# schody_v2.net
KiCad netlist of a schematic drawn in EAGLE
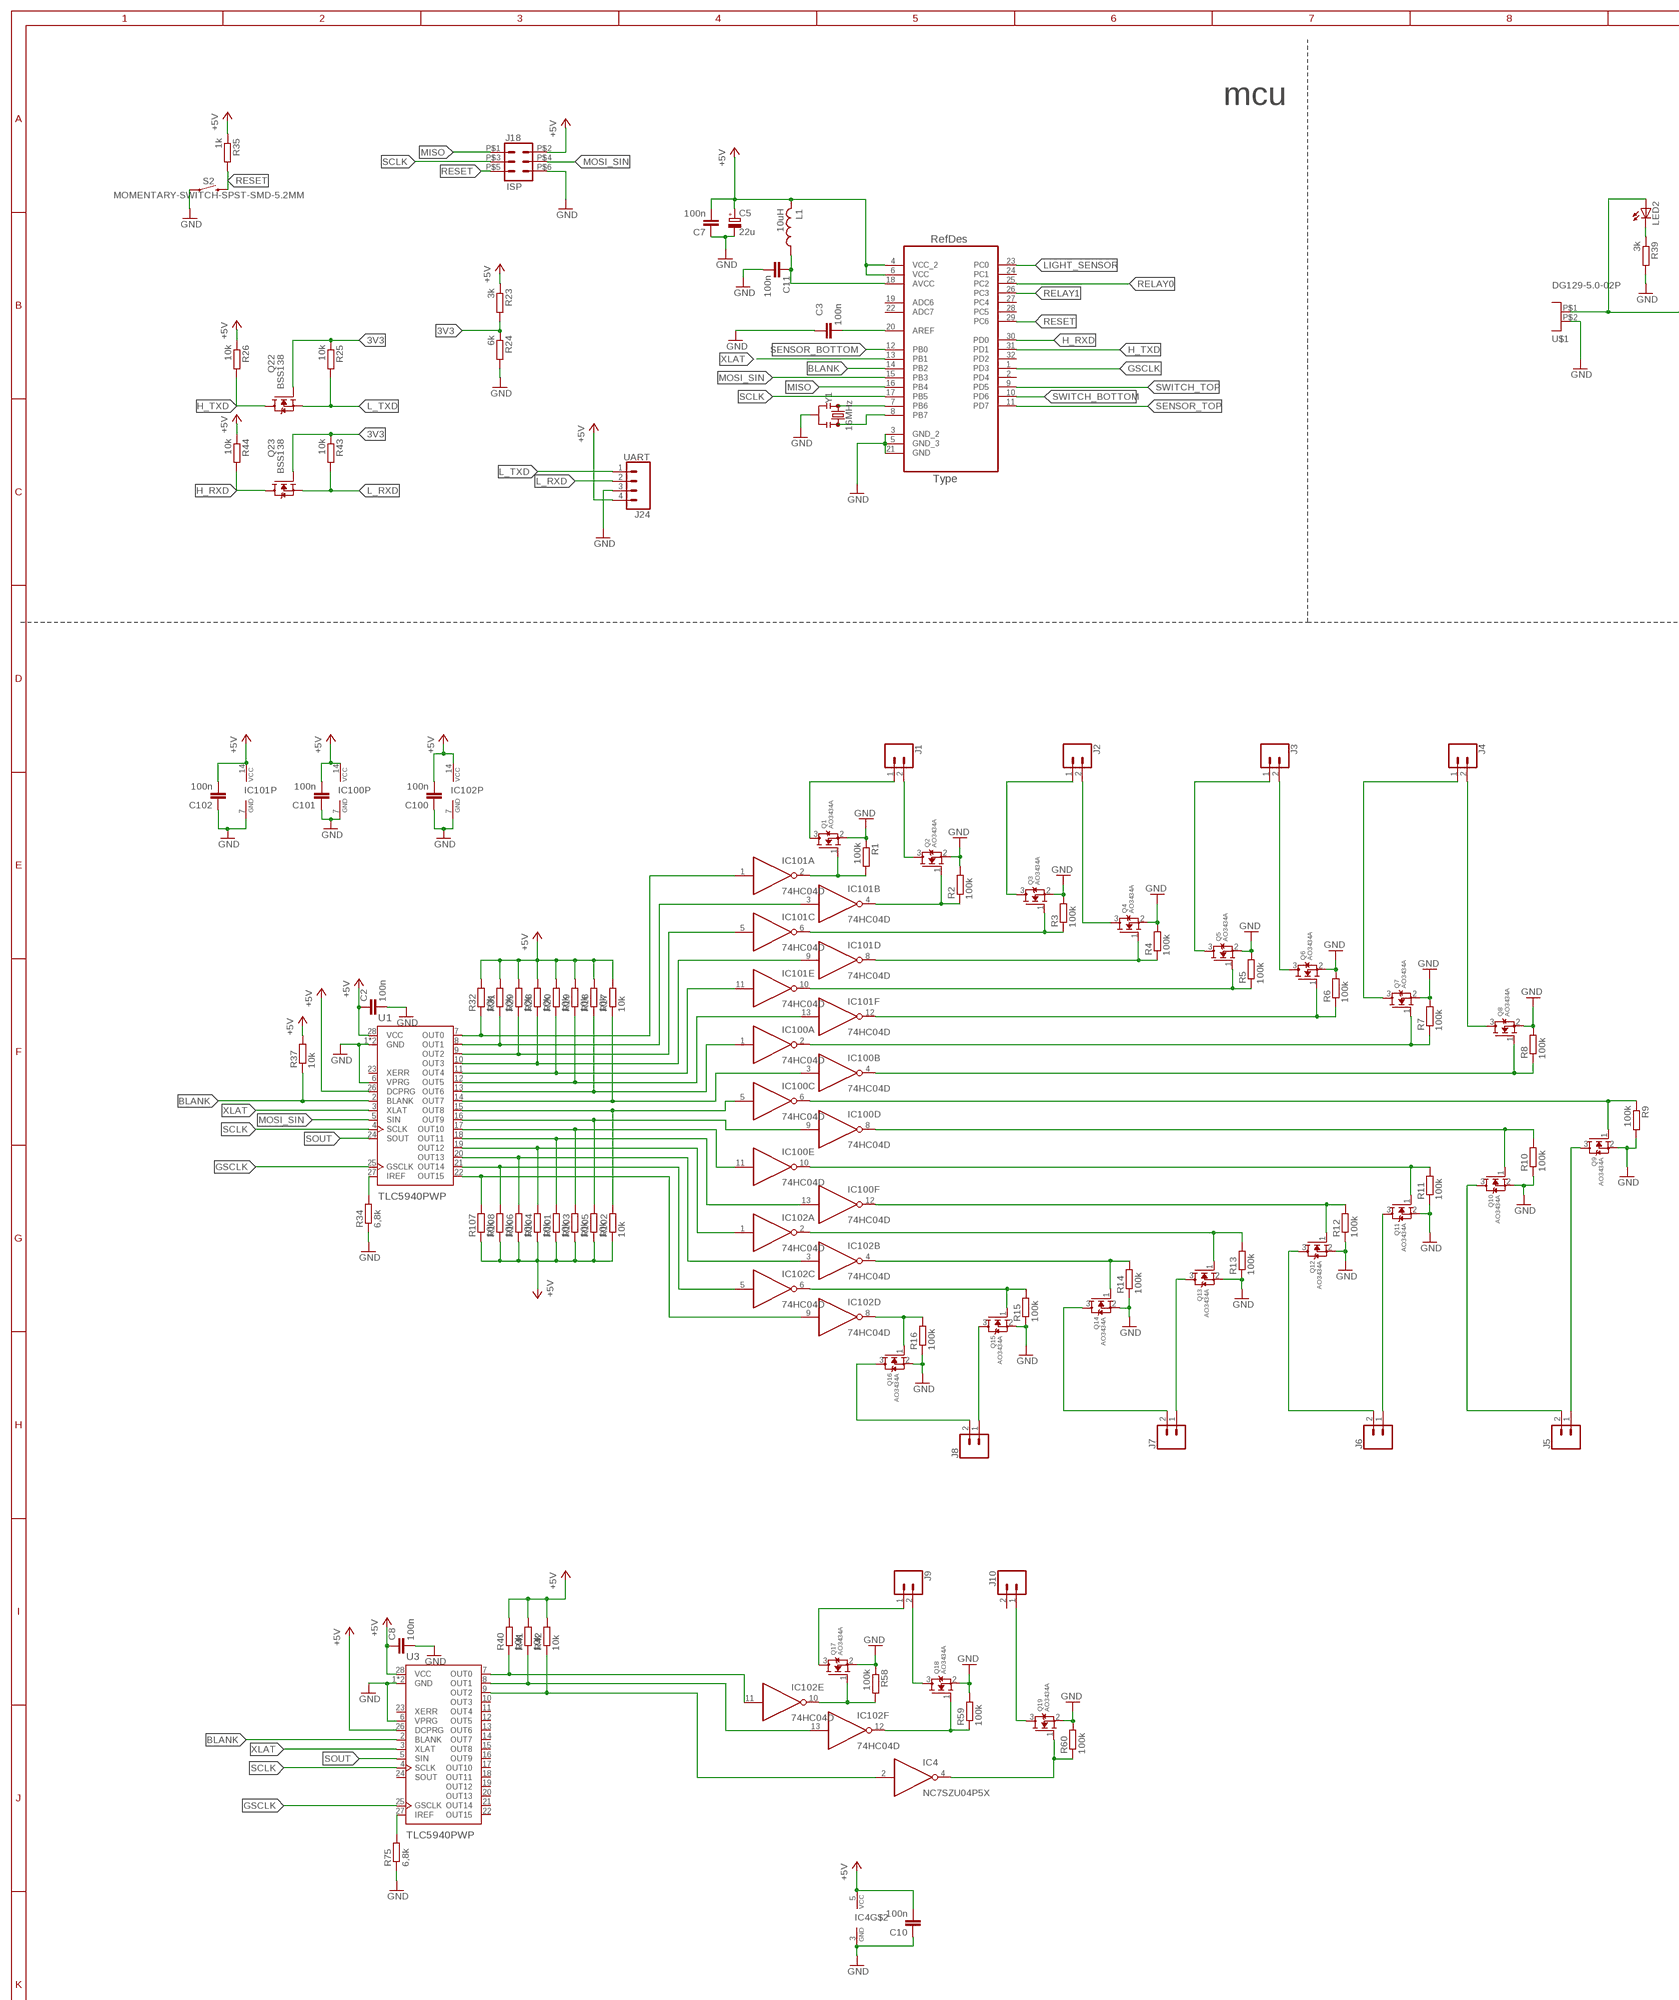
[diagram p0: schematic, sheet 1, part 1 of 3]
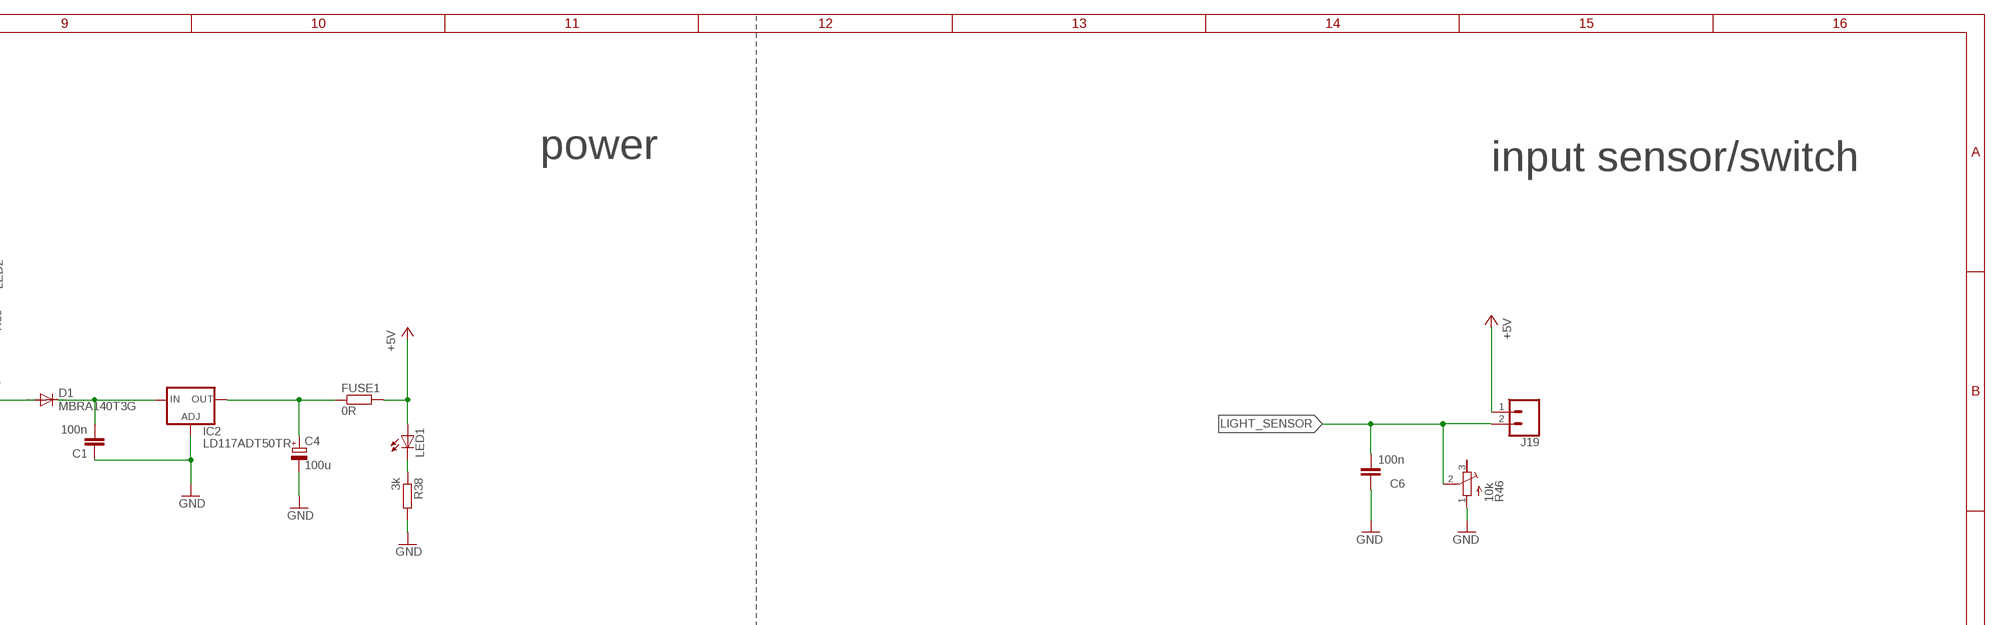
[diagram p1: schematic, sheet 1, part 2 of 3]
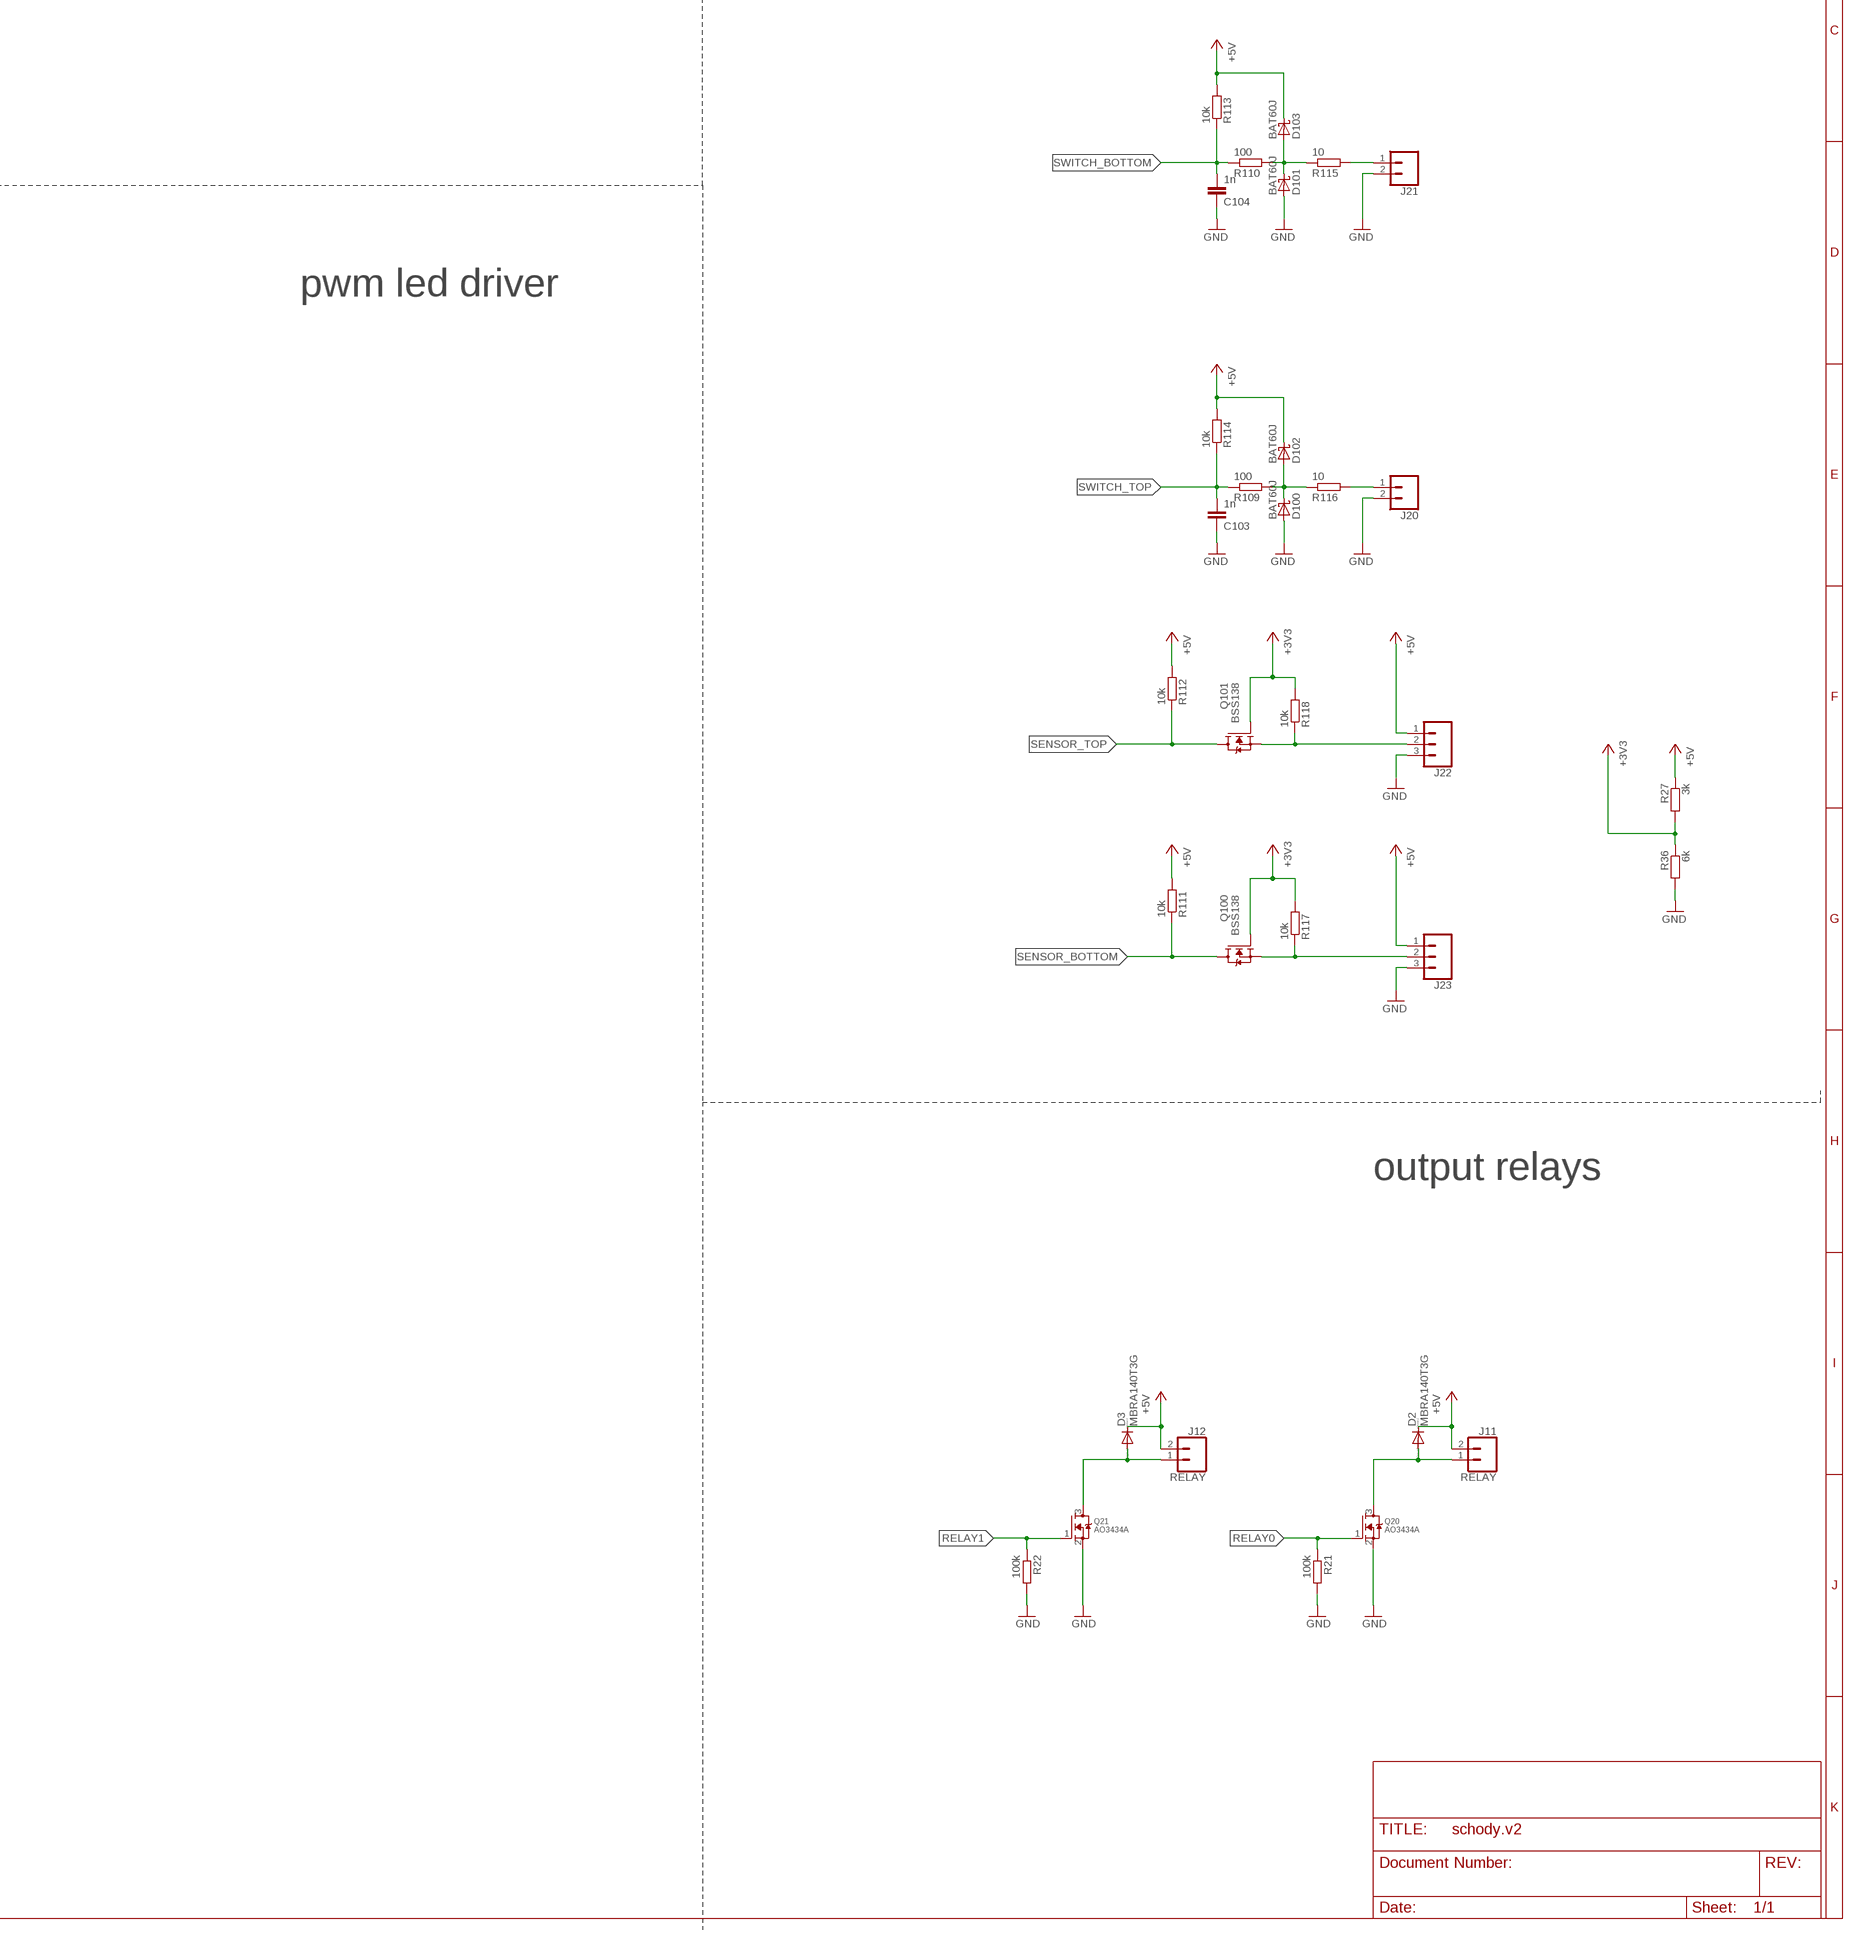
[diagram p2: schematic, sheet 1, part 3 of 3]

(export (version "E")
  (design (tool "Eeschema 10.0.6"))
  (components
    (comp (ref "C1")
      (value "100n")
      (footprint "eagle-import:C0805K")
      (libsource (lib "eagle-import") (part "C-EUC0805K"))
    )
    (comp (ref "C2")
      (value "100n")
      (footprint "eagle-import:C0805K")
      (libsource (lib "eagle-import") (part "C-EUC0805K"))
    )
    (comp (ref "C3")
      (value "100n")
      (footprint "eagle-import:C0805")
      (libsource (lib "eagle-import") (part "C-EUC0805"))
    )
    (comp (ref "C4")
      (value "100u")
      (footprint "eagle-import:SMC_D")
      (libsource (lib "eagle-import") (part "CPOL-EUSMCD"))
    )
    (comp (ref "C5")
      (value "22u")
      (footprint "eagle-import:SMC_E")
      (libsource (lib "eagle-import") (part "CPOL-EUSMCE"))
    )
    (comp (ref "C6")
      (value "100n")
      (footprint "eagle-import:C0805")
      (libsource (lib "eagle-import") (part "C-EUC0805"))
    )
    (comp (ref "C7")
      (value "100n")
      (footprint "eagle-import:C0805")
      (libsource (lib "eagle-import") (part "C-EUC0805"))
    )
    (comp (ref "C8")
      (value "100n")
      (footprint "eagle-import:C0805K")
      (libsource (lib "eagle-import") (part "C-EUC0805K"))
    )
    (comp (ref "C10")
      (value "100n")
      (footprint "eagle-import:C0805K")
      (libsource (lib "eagle-import") (part "C-EUC0805K"))
    )
    (comp (ref "C11")
      (value "100n")
      (footprint "eagle-import:C0805")
      (libsource (lib "eagle-import") (part "C-EUC0805"))
    )
    (comp (ref "C100")
      (value "100n")
      (footprint "eagle-import:C0805K")
      (libsource (lib "eagle-import") (part "C-EUC0805K"))
    )
    (comp (ref "C101")
      (value "100n")
      (footprint "eagle-import:C0805K")
      (libsource (lib "eagle-import") (part "C-EUC0805K"))
    )
    (comp (ref "C102")
      (value "100n")
      (footprint "eagle-import:C0805K")
      (libsource (lib "eagle-import") (part "C-EUC0805K"))
    )
    (comp (ref "C103")
      (value "1n")
      (footprint "eagle-import:C0805K")
      (libsource (lib "eagle-import") (part "C-EUC0805K"))
    )
    (comp (ref "C104")
      (value "1n")
      (footprint "eagle-import:C0805K")
      (libsource (lib "eagle-import") (part "C-EUC0805K"))
    )
    (comp (ref "D1")
      (value "MBRA140T3G")
      (footprint "eagle-import:DO214BA")
      (libsource (lib "eagle-import") (part "DIODE-DO214BA"))
    )
    (comp (ref "D2")
      (value "MBRA140T3G")
      (footprint "eagle-import:DO214BA")
      (libsource (lib "eagle-import") (part "DIODE-DO214BA"))
    )
    (comp (ref "D3")
      (value "MBRA140T3G")
      (footprint "eagle-import:DO214BA")
      (libsource (lib "eagle-import") (part "DIODE-DO214BA"))
    )
    (comp (ref "D100")
      (value "BAT60J")
      (footprint "eagle-import:SOD323_ST")
      (fields (field (name "SPICEPREFIX") "D"))
      (libsource (lib "eagle-import") (part "BAT60J"))
    )
    (comp (ref "D101")
      (value "BAT60J")
      (footprint "eagle-import:SOD323_ST")
      (libsource (lib "eagle-import") (part "BAT60J"))
    )
    (comp (ref "D102")
      (value "BAT60J")
      (footprint "eagle-import:SOD323_ST")
      (fields (field (name "SPICEPREFIX") "D"))
      (libsource (lib "eagle-import") (part "BAT60J"))
    )
    (comp (ref "D103")
      (value "BAT60J")
      (footprint "eagle-import:SOD323_ST")
      (libsource (lib "eagle-import") (part "BAT60J"))
    )
    (comp (ref "FUSE1")
      (value "0R")
      (footprint "eagle-import:M1206")
      (libsource (lib "eagle-import") (part "R-EU_M1206"))
    )
    (comp (ref "IC2")
      (value "LD117ADT50TR")
      (footprint "eagle-import:DPACK")
      (libsource (lib "eagle-import") (part "LD117A?DT50TR"))
    )
    (comp (ref "IC4")
      (value "NC7SZU04P5X")
      (footprint "eagle-import:SC70-5")
      (libsource (lib "eagle-import") (part "741GU04DCKAHC"))
    )
    (comp (ref "IC100")
      (value "74HC04D")
      (footprint "eagle-import:SO14")
      (libsource (lib "eagle-import") (part "7404DHC"))
    )
    (comp (ref "IC101")
      (value "74HC04D")
      (footprint "eagle-import:SO14")
      (libsource (lib "eagle-import") (part "7404DHC"))
    )
    (comp (ref "IC102")
      (value "74HC04D")
      (footprint "eagle-import:SO14")
      (libsource (lib "eagle-import") (part "7404DHC"))
    )
    (comp (ref "J1")
      (value "CONN_023.5MM")
      (footprint "eagle-import:SCREWTERMINAL-3.5MM-2")
      (libsource (lib "eagle-import") (part "CONN_023.5MM"))
    )
    (comp (ref "J2")
      (value "CONN_023.5MM")
      (footprint "eagle-import:SCREWTERMINAL-3.5MM-2")
      (libsource (lib "eagle-import") (part "CONN_023.5MM"))
    )
    (comp (ref "J3")
      (value "CONN_023.5MM")
      (footprint "eagle-import:SCREWTERMINAL-3.5MM-2")
      (libsource (lib "eagle-import") (part "CONN_023.5MM"))
    )
    (comp (ref "J4")
      (value "CONN_023.5MM")
      (footprint "eagle-import:SCREWTERMINAL-3.5MM-2")
      (libsource (lib "eagle-import") (part "CONN_023.5MM"))
    )
    (comp (ref "J5")
      (value "CONN_023.5MM")
      (footprint "eagle-import:SCREWTERMINAL-3.5MM-2")
      (libsource (lib "eagle-import") (part "CONN_023.5MM"))
    )
    (comp (ref "J6")
      (value "CONN_023.5MM")
      (footprint "eagle-import:SCREWTERMINAL-3.5MM-2")
      (libsource (lib "eagle-import") (part "CONN_023.5MM"))
    )
    (comp (ref "J7")
      (value "CONN_023.5MM")
      (footprint "eagle-import:SCREWTERMINAL-3.5MM-2")
      (libsource (lib "eagle-import") (part "CONN_023.5MM"))
    )
    (comp (ref "J8")
      (value "CONN_023.5MM")
      (footprint "eagle-import:SCREWTERMINAL-3.5MM-2")
      (libsource (lib "eagle-import") (part "CONN_023.5MM"))
    )
    (comp (ref "J9")
      (value "CONN_023.5MM")
      (footprint "eagle-import:SCREWTERMINAL-3.5MM-2")
      (libsource (lib "eagle-import") (part "CONN_023.5MM"))
    )
    (comp (ref "J10")
      (value "CONN_023.5MM")
      (footprint "eagle-import:SCREWTERMINAL-3.5MM-2")
      (libsource (lib "eagle-import") (part "CONN_023.5MM"))
    )
    (comp (ref "J11")
      (value "RELAY")
      (footprint "eagle-import:SCREWTERMINAL-3.5MM-2")
      (libsource (lib "eagle-import") (part "CONN_023.5MM"))
    )
    (comp (ref "J12")
      (value "RELAY")
      (footprint "eagle-import:SCREWTERMINAL-3.5MM-2")
      (libsource (lib "eagle-import") (part "CONN_023.5MM"))
    )
    (comp (ref "J18")
      (value "ISP")
      (footprint "eagle-import:2X3_POGO")
      (libsource (lib "eagle-import") (part "CONN_03X2POGO_PINS"))
    )
    (comp (ref "J19")
      (value "CONN_023.5MM")
      (footprint "eagle-import:SCREWTERMINAL-3.5MM-2")
      (libsource (lib "eagle-import") (part "CONN_023.5MM"))
    )
    (comp (ref "J20")
      (value "CONN_023.5MM")
      (footprint "eagle-import:SCREWTERMINAL-3.5MM-2")
      (libsource (lib "eagle-import") (part "CONN_023.5MM"))
    )
    (comp (ref "J21")
      (value "CONN_023.5MM")
      (footprint "eagle-import:SCREWTERMINAL-3.5MM-2")
      (libsource (lib "eagle-import") (part "CONN_023.5MM"))
    )
    (comp (ref "J22")
      (value "CONN_03SCREW")
      (footprint "eagle-import:SCREWTERMINAL-3.5MM-3")
      (libsource (lib "eagle-import") (part "CONN_03SCREW"))
    )
    (comp (ref "J23")
      (value "CONN_03SCREW")
      (footprint "eagle-import:SCREWTERMINAL-3.5MM-3")
      (libsource (lib "eagle-import") (part "CONN_03SCREW"))
    )
    (comp (ref "J24")
      (value "UART")
      (footprint "eagle-import:1X04")
      (libsource (lib "eagle-import") (part "CONN_04"))
    )
    (comp (ref "L1")
      (value "10uH")
      (footprint "eagle-import:0805")
      (libsource (lib "eagle-import") (part "L_USB"))
    )
    (comp (ref "LED1")
      (value "LEDCHIP-LED0805")
      (footprint "eagle-import:CHIP-LED0805")
      (libsource (lib "eagle-import") (part "LEDCHIP-LED0805"))
    )
    (comp (ref "LED2")
      (value "LEDCHIP-LED0805")
      (footprint "eagle-import:CHIP-LED0805")
      (libsource (lib "eagle-import") (part "LEDCHIP-LED0805"))
    )
    (comp (ref "Q1")
      (value "AO3434A")
      (footprint "eagle-import:SOT23-W")
      (libsource (lib "eagle-import") (part "MOSFET-NWAVE"))
    )
    (comp (ref "Q2")
      (value "AO3434A")
      (footprint "eagle-import:SOT23-W")
      (libsource (lib "eagle-import") (part "MOSFET-NWAVE"))
    )
    (comp (ref "Q3")
      (value "AO3434A")
      (footprint "eagle-import:SOT23-W")
      (libsource (lib "eagle-import") (part "MOSFET-NWAVE"))
    )
    (comp (ref "Q4")
      (value "AO3434A")
      (footprint "eagle-import:SOT23-W")
      (libsource (lib "eagle-import") (part "MOSFET-NWAVE"))
    )
    (comp (ref "Q5")
      (value "AO3434A")
      (footprint "eagle-import:SOT23-W")
      (libsource (lib "eagle-import") (part "MOSFET-NWAVE"))
    )
    (comp (ref "Q6")
      (value "AO3434A")
      (footprint "eagle-import:SOT23-W")
      (libsource (lib "eagle-import") (part "MOSFET-NWAVE"))
    )
    (comp (ref "Q7")
      (value "AO3434A")
      (footprint "eagle-import:SOT23-W")
      (libsource (lib "eagle-import") (part "MOSFET-NWAVE"))
    )
    (comp (ref "Q8")
      (value "AO3434A")
      (footprint "eagle-import:SOT23-W")
      (libsource (lib "eagle-import") (part "MOSFET-NWAVE"))
    )
    (comp (ref "Q9")
      (value "AO3434A")
      (footprint "eagle-import:SOT23-W")
      (libsource (lib "eagle-import") (part "MOSFET-NWAVE"))
    )
    (comp (ref "Q10")
      (value "AO3434A")
      (footprint "eagle-import:SOT23-W")
      (libsource (lib "eagle-import") (part "MOSFET-NWAVE"))
    )
    (comp (ref "Q11")
      (value "AO3434A")
      (footprint "eagle-import:SOT23-W")
      (libsource (lib "eagle-import") (part "MOSFET-NWAVE"))
    )
    (comp (ref "Q12")
      (value "AO3434A")
      (footprint "eagle-import:SOT23-W")
      (libsource (lib "eagle-import") (part "MOSFET-NWAVE"))
    )
    (comp (ref "Q13")
      (value "AO3434A")
      (footprint "eagle-import:SOT23-W")
      (libsource (lib "eagle-import") (part "MOSFET-NWAVE"))
    )
    (comp (ref "Q14")
      (value "AO3434A")
      (footprint "eagle-import:SOT23-W")
      (libsource (lib "eagle-import") (part "MOSFET-NWAVE"))
    )
    (comp (ref "Q15")
      (value "AO3434A")
      (footprint "eagle-import:SOT23-W")
      (libsource (lib "eagle-import") (part "MOSFET-NWAVE"))
    )
    (comp (ref "Q16")
      (value "AO3434A")
      (footprint "eagle-import:SOT23-W")
      (libsource (lib "eagle-import") (part "MOSFET-NWAVE"))
    )
    (comp (ref "Q17")
      (value "AO3434A")
      (footprint "eagle-import:SOT23-W")
      (libsource (lib "eagle-import") (part "MOSFET-NWAVE"))
    )
    (comp (ref "Q18")
      (value "AO3434A")
      (footprint "eagle-import:SOT23-W")
      (libsource (lib "eagle-import") (part "MOSFET-NWAVE"))
    )
    (comp (ref "Q19")
      (value "AO3434A")
      (footprint "eagle-import:SOT23-W")
      (libsource (lib "eagle-import") (part "MOSFET-NWAVE"))
    )
    (comp (ref "Q20")
      (value "AO3434A")
      (footprint "eagle-import:SOT23-W")
      (libsource (lib "eagle-import") (part "MOSFET-NWAVE"))
    )
    (comp (ref "Q21")
      (value "AO3434A")
      (footprint "eagle-import:SOT23-W")
      (libsource (lib "eagle-import") (part "MOSFET-NWAVE"))
    )
    (comp (ref "Q22")
      (value "BSS138")
      (footprint "eagle-import:SOT23")
      (fields (field (name "MF") "Fairchild"))
      (libsource (lib "eagle-import") (part "BSS138"))
    )
    (comp (ref "Q23")
      (value "BSS138")
      (footprint "eagle-import:SOT23")
      (fields (field (name "MF") "Fairchild"))
      (libsource (lib "eagle-import") (part "BSS138"))
    )
    (comp (ref "Q100")
      (value "BSS138")
      (footprint "eagle-import:SOT23")
      (fields (field (name "MF") "Fairchild"))
      (libsource (lib "eagle-import") (part "BSS138"))
    )
    (comp (ref "Q101")
      (value "BSS138")
      (footprint "eagle-import:SOT23")
      (fields (field (name "MF") "Fairchild"))
      (libsource (lib "eagle-import") (part "BSS138"))
    )
    (comp (ref "R1")
      (value "100k")
      (footprint "eagle-import:M0805")
      (libsource (lib "eagle-import") (part "resistor_348_R-EU_M0805"))
    )
    (comp (ref "R2")
      (value "100k")
      (footprint "eagle-import:M0805")
      (libsource (lib "eagle-import") (part "resistor_348_R-EU_M0805"))
    )
    (comp (ref "R3")
      (value "100k")
      (footprint "eagle-import:M0805")
      (libsource (lib "eagle-import") (part "resistor_348_R-EU_M0805"))
    )
    (comp (ref "R4")
      (value "100k")
      (footprint "eagle-import:M0805")
      (libsource (lib "eagle-import") (part "resistor_348_R-EU_M0805"))
    )
    (comp (ref "R5")
      (value "100k")
      (footprint "eagle-import:M0805")
      (libsource (lib "eagle-import") (part "resistor_348_R-EU_M0805"))
    )
    (comp (ref "R6")
      (value "100k")
      (footprint "eagle-import:M0805")
      (libsource (lib "eagle-import") (part "resistor_348_R-EU_M0805"))
    )
    (comp (ref "R7")
      (value "100k")
      (footprint "eagle-import:M0805")
      (libsource (lib "eagle-import") (part "resistor_348_R-EU_M0805"))
    )
    (comp (ref "R8")
      (value "100k")
      (footprint "eagle-import:M0805")
      (libsource (lib "eagle-import") (part "resistor_348_R-EU_M0805"))
    )
    (comp (ref "R9")
      (value "100k")
      (footprint "eagle-import:M0805")
      (libsource (lib "eagle-import") (part "resistor_348_R-EU_M0805"))
    )
    (comp (ref "R10")
      (value "100k")
      (footprint "eagle-import:M0805")
      (libsource (lib "eagle-import") (part "resistor_348_R-EU_M0805"))
    )
    (comp (ref "R11")
      (value "100k")
      (footprint "eagle-import:M0805")
      (libsource (lib "eagle-import") (part "resistor_348_R-EU_M0805"))
    )
    (comp (ref "R12")
      (value "100k")
      (footprint "eagle-import:M0805")
      (libsource (lib "eagle-import") (part "resistor_348_R-EU_M0805"))
    )
    (comp (ref "R13")
      (value "100k")
      (footprint "eagle-import:M0805")
      (libsource (lib "eagle-import") (part "resistor_348_R-EU_M0805"))
    )
    (comp (ref "R14")
      (value "100k")
      (footprint "eagle-import:M0805")
      (libsource (lib "eagle-import") (part "resistor_348_R-EU_M0805"))
    )
    (comp (ref "R15")
      (value "100k")
      (footprint "eagle-import:M0805")
      (libsource (lib "eagle-import") (part "resistor_348_R-EU_M0805"))
    )
    (comp (ref "R16")
      (value "100k")
      (footprint "eagle-import:M0805")
      (libsource (lib "eagle-import") (part "resistor_348_R-EU_M0805"))
    )
    (comp (ref "R17")
      (value "10k")
      (footprint "eagle-import:M0805")
      (libsource (lib "eagle-import") (part "resistor_348_R-EU_M0805"))
    )
    (comp (ref "R18")
      (value "10k")
      (footprint "eagle-import:M0805")
      (libsource (lib "eagle-import") (part "resistor_348_R-EU_M0805"))
    )
    (comp (ref "R19")
      (value "10k")
      (footprint "eagle-import:M0805")
      (libsource (lib "eagle-import") (part "resistor_348_R-EU_M0805"))
    )
    (comp (ref "R20")
      (value "10k")
      (footprint "eagle-import:M0805")
      (libsource (lib "eagle-import") (part "resistor_348_R-EU_M0805"))
    )
    (comp (ref "R21")
      (value "100k")
      (footprint "eagle-import:M0805")
      (libsource (lib "eagle-import") (part "R-EU_M0805"))
    )
    (comp (ref "R22")
      (value "100k")
      (footprint "eagle-import:M0805")
      (libsource (lib "eagle-import") (part "R-EU_M0805"))
    )
    (comp (ref "R23")
      (value "3k")
      (footprint "eagle-import:M0805")
      (libsource (lib "eagle-import") (part "R-EU_M0805"))
    )
    (comp (ref "R24")
      (value "6k")
      (footprint "eagle-import:M0805")
      (libsource (lib "eagle-import") (part "R-EU_M0805"))
    )
    (comp (ref "R25")
      (value "10k")
      (footprint "eagle-import:M0805")
      (libsource (lib "eagle-import") (part "R-EU_M0805"))
    )
    (comp (ref "R26")
      (value "10k")
      (footprint "eagle-import:M0805")
      (libsource (lib "eagle-import") (part "R-EU_M0805"))
    )
    (comp (ref "R27")
      (value "3k")
      (footprint "eagle-import:M0805")
      (libsource (lib "eagle-import") (part "R-EU_M0805"))
    )
    (comp (ref "R28")
      (value "10k")
      (footprint "eagle-import:M0805")
      (libsource (lib "eagle-import") (part "resistor_348_R-EU_M0805"))
    )
    (comp (ref "R29")
      (value "10k")
      (footprint "eagle-import:M0805")
      (libsource (lib "eagle-import") (part "resistor_348_R-EU_M0805"))
    )
    (comp (ref "R31")
      (value "10k")
      (footprint "eagle-import:M0805")
      (libsource (lib "eagle-import") (part "resistor_348_R-EU_M0805"))
    )
    (comp (ref "R32")
      (value "10k")
      (footprint "eagle-import:M0805")
      (libsource (lib "eagle-import") (part "resistor_348_R-EU_M0805"))
    )
    (comp (ref "R34")
      (value "6,8k")
      (footprint "eagle-import:M0805")
      (libsource (lib "eagle-import") (part "resistor_348_R-EU_M0805"))
    )
    (comp (ref "R35")
      (value "1k")
      (footprint "eagle-import:M0805")
      (libsource (lib "eagle-import") (part "R-EU_M0805"))
    )
    (comp (ref "R36")
      (value "6k")
      (footprint "eagle-import:M0805")
      (libsource (lib "eagle-import") (part "R-EU_M0805"))
    )
    (comp (ref "R37")
      (value "10k")
      (footprint "eagle-import:M0805")
      (libsource (lib "eagle-import") (part "resistor_348_R-EU_M0805"))
    )
    (comp (ref "R38")
      (value "3k")
      (footprint "eagle-import:M0805")
      (libsource (lib "eagle-import") (part "R-EU_M0805"))
    )
    (comp (ref "R39")
      (value "3k")
      (footprint "eagle-import:M0805")
      (libsource (lib "eagle-import") (part "R-EU_M0805"))
    )
    (comp (ref "R40")
      (value "10k")
      (footprint "eagle-import:M0805")
      (libsource (lib "eagle-import") (part "resistor_348_R-EU_M0805"))
    )
    (comp (ref "R41")
      (value "10k")
      (footprint "eagle-import:M0805")
      (libsource (lib "eagle-import") (part "resistor_348_R-EU_M0805"))
    )
    (comp (ref "R42")
      (value "10k")
      (footprint "eagle-import:M0805")
      (libsource (lib "eagle-import") (part "resistor_348_R-EU_M0805"))
    )
    (comp (ref "R43")
      (value "10k")
      (footprint "eagle-import:M0805")
      (libsource (lib "eagle-import") (part "R-EU_M0805"))
    )
    (comp (ref "R44")
      (value "10k")
      (footprint "eagle-import:M0805")
      (libsource (lib "eagle-import") (part "R-EU_M0805"))
    )
    (comp (ref "R46")
      (value "10k")
      (footprint "eagle-import:RTRIM64W")
      (libsource (lib "eagle-import") (part "R-TRIMM64W"))
    )
    (comp (ref "R58")
      (value "100k")
      (footprint "eagle-import:M0805")
      (libsource (lib "eagle-import") (part "resistor_348_R-EU_M0805"))
    )
    (comp (ref "R59")
      (value "100k")
      (footprint "eagle-import:M0805")
      (libsource (lib "eagle-import") (part "resistor_348_R-EU_M0805"))
    )
    (comp (ref "R60")
      (value "100k")
      (footprint "eagle-import:M0805")
      (libsource (lib "eagle-import") (part "resistor_348_R-EU_M0805"))
    )
    (comp (ref "R75")
      (value "6,8k")
      (footprint "eagle-import:M0805")
      (libsource (lib "eagle-import") (part "resistor_348_R-EU_M0805"))
    )
    (comp (ref "R101")
      (value "10k")
      (footprint "eagle-import:M0805")
      (libsource (lib "eagle-import") (part "resistor_348_R-EU_M0805"))
    )
    (comp (ref "R102")
      (value "10k")
      (footprint "eagle-import:M0805")
      (libsource (lib "eagle-import") (part "resistor_348_R-EU_M0805"))
    )
    (comp (ref "R103")
      (value "10k")
      (footprint "eagle-import:M0805")
      (libsource (lib "eagle-import") (part "resistor_348_R-EU_M0805"))
    )
    (comp (ref "R104")
      (value "10k")
      (footprint "eagle-import:M0805")
      (libsource (lib "eagle-import") (part "resistor_348_R-EU_M0805"))
    )
    (comp (ref "R105")
      (value "10k")
      (footprint "eagle-import:M0805")
      (libsource (lib "eagle-import") (part "resistor_348_R-EU_M0805"))
    )
    (comp (ref "R106")
      (value "10k")
      (footprint "eagle-import:M0805")
      (libsource (lib "eagle-import") (part "resistor_348_R-EU_M0805"))
    )
    (comp (ref "R107")
      (value "10k")
      (footprint "eagle-import:M0805")
      (libsource (lib "eagle-import") (part "resistor_348_R-EU_M0805"))
    )
    (comp (ref "R108")
      (value "10k")
      (footprint "eagle-import:M0805")
      (libsource (lib "eagle-import") (part "resistor_348_R-EU_M0805"))
    )
    (comp (ref "R109")
      (value "100")
      (footprint "eagle-import:M0805")
      (fields (field (name "SPICEPREFIX") "R"))
      (libsource (lib "eagle-import") (part "resistor_348_R-EU_M0805"))
    )
    (comp (ref "R110")
      (value "100")
      (footprint "eagle-import:M0805")
      (libsource (lib "eagle-import") (part "resistor_348_R-EU_M0805"))
    )
    (comp (ref "R111")
      (value "10k")
      (footprint "eagle-import:M0805")
      (libsource (lib "eagle-import") (part "resistor_348_R-EU_M0805"))
    )
    (comp (ref "R112")
      (value "10k")
      (footprint "eagle-import:M0805")
      (libsource (lib "eagle-import") (part "resistor_348_R-EU_M0805"))
    )
    (comp (ref "R113")
      (value "10k")
      (footprint "eagle-import:M0805")
      (libsource (lib "eagle-import") (part "resistor_348_R-EU_M0805"))
    )
    (comp (ref "R114")
      (value "10k")
      (footprint "eagle-import:M0805")
      (fields (field (name "SPICEPREFIX") "R"))
      (libsource (lib "eagle-import") (part "resistor_348_R-EU_M0805"))
    )
    (comp (ref "R115")
      (value "10")
      (footprint "eagle-import:M0805")
      (libsource (lib "eagle-import") (part "resistor_348_R-EU_M0805"))
    )
    (comp (ref "R116")
      (value "10")
      (footprint "eagle-import:M0805")
      (fields (field (name "SPICEPREFIX") "R"))
      (libsource (lib "eagle-import") (part "resistor_348_R-EU_M0805"))
    )
    (comp (ref "R117")
      (value "10k")
      (footprint "eagle-import:M0805")
      (libsource (lib "eagle-import") (part "resistor_348_R-EU_M0805"))
    )
    (comp (ref "R118")
      (value "10k")
      (footprint "eagle-import:M0805")
      (libsource (lib "eagle-import") (part "resistor_348_R-EU_M0805"))
    )
    (comp (ref "S2")
      (value "MOMENTARY-SWITCH-SPST-SMD-5.2MM")
      (footprint "eagle-import:TACTILE_SWITCH_SMD_5.2MM")
      (libsource (lib "eagle-import") (part "MOMENTARY-SWITCH-SPST-SMD-5.2MM"))
    )
    (comp (ref "U$1")
      (value "DG129-5.0-02P")
      (footprint "eagle-import:DG129-5.0-02P")
      (libsource (lib "eagle-import") (part "DG129-5.0-02P"))
    )
    (comp (ref "U1")
      (value "TLC5940PWP")
      (footprint "eagle-import:HTSSOP28PWP")
      (libsource (lib "eagle-import") (part "TLC5940PWP"))
    )
    (comp (ref "U2")
      (value "ATMEGA328P-AU")
      (footprint "eagle-import:QFP80P900X900X120-32N")
      (libsource (lib "eagle-import") (part "ATMEGA328P-AU"))
    )
    (comp (ref "U3")
      (value "TLC5940PWP")
      (footprint "eagle-import:HTSSOP28PWP")
      (libsource (lib "eagle-import") (part "TLC5940PWP"))
    )
    (comp (ref "Y1")
      (value "16MHz")
      (footprint "eagle-import:RESONATOR-SMD-3.2X1.3")
      (libsource (lib "eagle-import") (part "RESONATOR-16MHZSMD_3.2X1.3"))
    )
  )
  (nets
    (net (code "1") (name "+3V3") (class "Default")
      (node (ref "Q100") (pin "1") (pinfunction "G_1") (pintype "passive"))
      (node (ref "Q101") (pin "1") (pinfunction "G_1") (pintype "passive"))
      (node (ref "R117") (pin "2") (pinfunction "2_2") (pintype "passive"))
      (node (ref "R118") (pin "2") (pinfunction "2_2") (pintype "passive"))
      (node (ref "R27") (pin "2") (pinfunction "2_2") (pintype "passive"))
      (node (ref "R36") (pin "1") (pinfunction "1_1") (pintype "passive"))
    )
    (net (code "2") (name "+5V") (class "Default")
      (node (ref "C10") (pin "2") (pinfunction "2_2") (pintype "passive"))
      (node (ref "C100") (pin "2") (pinfunction "2_2") (pintype "passive"))
      (node (ref "C101") (pin "2") (pinfunction "2_2") (pintype "passive"))
      (node (ref "C102") (pin "2") (pinfunction "2_2") (pintype "passive"))
      (node (ref "C2") (pin "1") (pinfunction "1_1") (pintype "passive"))
      (node (ref "C5") (pin "+") (pinfunction "+_+") (pintype "passive"))
      (node (ref "C7") (pin "2") (pinfunction "2_2") (pintype "passive"))
      (node (ref "C8") (pin "1") (pinfunction "1_1") (pintype "passive"))
      (node (ref "D102") (pin "C") (pinfunction "C_C") (pintype "passive"))
      (node (ref "D103") (pin "C") (pinfunction "C_C") (pintype "passive"))
      (node (ref "D2") (pin "C") (pinfunction "C_C") (pintype "passive"))
      (node (ref "D3") (pin "C") (pinfunction "C_C") (pintype "passive"))
      (node (ref "FUSE1") (pin "2") (pinfunction "2_2") (pintype "passive"))
      (node (ref "IC100") (pin "14") (pinfunction "VCC_14") (pintype "power_in"))
      (node (ref "IC101") (pin "14") (pinfunction "VCC_14") (pintype "power_in"))
      (node (ref "IC102") (pin "14") (pinfunction "VCC_14") (pintype "power_in"))
      (node (ref "IC4") (pin "5") (pinfunction "VCC_5") (pintype "power_in"))
      (node (ref "J11") (pin "2") (pinfunction "2_2") (pintype "passive"))
      (node (ref "J12") (pin "2") (pinfunction "2_2") (pintype "passive"))
      (node (ref "J18") (pin "P$2") (pinfunction "2_P$2") (pintype "bidirectional"))
      (node (ref "J19") (pin "1") (pinfunction "1_1") (pintype "passive"))
      (node (ref "J22") (pin "1") (pinfunction "1_1") (pintype "passive"))
      (node (ref "J23") (pin "1") (pinfunction "1_1") (pintype "passive"))
      (node (ref "J24") (pin "4") (pinfunction "4_4") (pintype "passive"))
      (node (ref "L1") (pin "2") (pinfunction "2_2") (pintype "passive"))
      (node (ref "LED1") (pin "A") (pinfunction "A_A") (pintype "passive"))
      (node (ref "R101") (pin "1") (pinfunction "1_1") (pintype "passive"))
      (node (ref "R102") (pin "1") (pinfunction "1_1") (pintype "passive"))
      (node (ref "R103") (pin "1") (pinfunction "1_1") (pintype "passive"))
      (node (ref "R104") (pin "1") (pinfunction "1_1") (pintype "passive"))
      (node (ref "R105") (pin "1") (pinfunction "1_1") (pintype "passive"))
      (node (ref "R106") (pin "1") (pinfunction "1_1") (pintype "passive"))
      (node (ref "R107") (pin "1") (pinfunction "1_1") (pintype "passive"))
      (node (ref "R108") (pin "1") (pinfunction "1_1") (pintype "passive"))
      (node (ref "R111") (pin "2") (pinfunction "2_2") (pintype "passive"))
      (node (ref "R112") (pin "2") (pinfunction "2_2") (pintype "passive"))
      (node (ref "R113") (pin "2") (pinfunction "2_2") (pintype "passive"))
      (node (ref "R114") (pin "2") (pinfunction "2_2") (pintype "passive"))
      (node (ref "R17") (pin "2") (pinfunction "2_2") (pintype "passive"))
      (node (ref "R18") (pin "2") (pinfunction "2_2") (pintype "passive"))
      (node (ref "R19") (pin "2") (pinfunction "2_2") (pintype "passive"))
      (node (ref "R20") (pin "2") (pinfunction "2_2") (pintype "passive"))
      (node (ref "R23") (pin "1") (pinfunction "1_1") (pintype "passive"))
      (node (ref "R26") (pin "1") (pinfunction "1_1") (pintype "passive"))
      (node (ref "R27") (pin "1") (pinfunction "1_1") (pintype "passive"))
      (node (ref "R28") (pin "2") (pinfunction "2_2") (pintype "passive"))
      (node (ref "R29") (pin "2") (pinfunction "2_2") (pintype "passive"))
      (node (ref "R31") (pin "2") (pinfunction "2_2") (pintype "passive"))
      (node (ref "R32") (pin "2") (pinfunction "2_2") (pintype "passive"))
      (node (ref "R35") (pin "1") (pinfunction "1_1") (pintype "passive"))
      (node (ref "R37") (pin "2") (pinfunction "2_2") (pintype "passive"))
      (node (ref "R40") (pin "2") (pinfunction "2_2") (pintype "passive"))
      (node (ref "R41") (pin "2") (pinfunction "2_2") (pintype "passive"))
      (node (ref "R42") (pin "2") (pinfunction "2_2") (pintype "passive"))
      (node (ref "R44") (pin "1") (pinfunction "1_1") (pintype "passive"))
      (node (ref "U1") (pin "26") (pinfunction "DCPRG_26") (pintype "input"))
      (node (ref "U1") (pin "28") (pinfunction "VCC_28") (pintype "power_in"))
      (node (ref "U2") (pin "4") (pinfunction "VCC_2_4") (pintype "power_in"))
      (node (ref "U2") (pin "6") (pinfunction "VCC_6") (pintype "power_in"))
      (node (ref "U3") (pin "26") (pinfunction "DCPRG_26") (pintype "input"))
      (node (ref "U3") (pin "28") (pinfunction "VCC_28") (pintype "power_in"))
    )
    (net (code "3") (name "3V3") (class "Default")
      (node (ref "Q22") (pin "1") (pinfunction "G_1") (pintype "passive"))
      (node (ref "Q23") (pin "1") (pinfunction "G_1") (pintype "passive"))
      (node (ref "R23") (pin "2") (pinfunction "2_2") (pintype "passive"))
      (node (ref "R24") (pin "1") (pinfunction "1_1") (pintype "passive"))
      (node (ref "R25") (pin "1") (pinfunction "1_1") (pintype "passive"))
      (node (ref "R43") (pin "1") (pinfunction "1_1") (pintype "passive"))
    )
    (net (code "4") (name "BLANK") (class "Default")
      (node (ref "R37") (pin "1") (pinfunction "1_1") (pintype "passive"))
      (node (ref "U1") (pin "2") (pinfunction "BLANK_2") (pintype "input"))
      (node (ref "U2") (pin "14") (pinfunction "PB2_14") (pintype "bidirectional"))
      (node (ref "U3") (pin "2") (pinfunction "BLANK_2") (pintype "input"))
    )
    (net (code "5") (name "GND") (class "Default")
      (node (ref "C1") (pin "1") (pinfunction "1_1") (pintype "passive"))
      (node (ref "C10") (pin "1") (pinfunction "1_1") (pintype "passive"))
      (node (ref "C100") (pin "1") (pinfunction "1_1") (pintype "passive"))
      (node (ref "C101") (pin "1") (pinfunction "1_1") (pintype "passive"))
      (node (ref "C102") (pin "1") (pinfunction "1_1") (pintype "passive"))
      (node (ref "C103") (pin "1") (pinfunction "1_1") (pintype "passive"))
      (node (ref "C104") (pin "1") (pinfunction "1_1") (pintype "passive"))
      (node (ref "C11") (pin "2") (pinfunction "2_2") (pintype "passive"))
      (node (ref "C2") (pin "2") (pinfunction "2_2") (pintype "passive"))
      (node (ref "C3") (pin "1") (pinfunction "1_1") (pintype "passive"))
      (node (ref "C4") (pin "-") (pinfunction "-_-") (pintype "passive"))
      (node (ref "C5") (pin "-") (pinfunction "-_-") (pintype "passive"))
      (node (ref "C6") (pin "1") (pinfunction "1_1") (pintype "passive"))
      (node (ref "C7") (pin "1") (pinfunction "1_1") (pintype "passive"))
      (node (ref "C8") (pin "2") (pinfunction "2_2") (pintype "passive"))
      (node (ref "D100") (pin "A") (pinfunction "A_A") (pintype "passive"))
      (node (ref "D101") (pin "A") (pinfunction "A_A") (pintype "passive"))
      (node (ref "IC100") (pin "7") (pinfunction "GND_7") (pintype "power_in"))
      (node (ref "IC101") (pin "7") (pinfunction "GND_7") (pintype "power_in"))
      (node (ref "IC102") (pin "7") (pinfunction "GND_7") (pintype "power_in"))
      (node (ref "IC2") (pin "1") (pinfunction "ADJ_1") (pintype "input"))
      (node (ref "IC4") (pin "3") (pinfunction "GND_3") (pintype "power_in"))
      (node (ref "J18") (pin "P$6") (pinfunction "6_P$6") (pintype "bidirectional"))
      (node (ref "J20") (pin "2") (pinfunction "2_2") (pintype "passive"))
      (node (ref "J21") (pin "2") (pinfunction "2_2") (pintype "passive"))
      (node (ref "J22") (pin "3") (pinfunction "3_3") (pintype "passive"))
      (node (ref "J23") (pin "3") (pinfunction "3_3") (pintype "passive"))
      (node (ref "J24") (pin "3") (pinfunction "3_3") (pintype "passive"))
      (node (ref "Q1") (pin "2") (pinfunction "S_2") (pintype "bidirectional"))
      (node (ref "Q10") (pin "2") (pinfunction "S_2") (pintype "bidirectional"))
      (node (ref "Q11") (pin "2") (pinfunction "S_2") (pintype "bidirectional"))
      (node (ref "Q12") (pin "2") (pinfunction "S_2") (pintype "bidirectional"))
      (node (ref "Q13") (pin "2") (pinfunction "S_2") (pintype "bidirectional"))
      (node (ref "Q14") (pin "2") (pinfunction "S_2") (pintype "bidirectional"))
      (node (ref "Q15") (pin "2") (pinfunction "S_2") (pintype "bidirectional"))
      (node (ref "Q16") (pin "2") (pinfunction "S_2") (pintype "bidirectional"))
      (node (ref "Q17") (pin "2") (pinfunction "S_2") (pintype "bidirectional"))
      (node (ref "Q18") (pin "2") (pinfunction "S_2") (pintype "bidirectional"))
      (node (ref "Q19") (pin "2") (pinfunction "S_2") (pintype "bidirectional"))
      (node (ref "Q2") (pin "2") (pinfunction "S_2") (pintype "bidirectional"))
      (node (ref "Q20") (pin "2") (pinfunction "S_2") (pintype "bidirectional"))
      (node (ref "Q21") (pin "2") (pinfunction "S_2") (pintype "bidirectional"))
      (node (ref "Q3") (pin "2") (pinfunction "S_2") (pintype "bidirectional"))
      (node (ref "Q4") (pin "2") (pinfunction "S_2") (pintype "bidirectional"))
      (node (ref "Q5") (pin "2") (pinfunction "S_2") (pintype "bidirectional"))
      (node (ref "Q6") (pin "2") (pinfunction "S_2") (pintype "bidirectional"))
      (node (ref "Q7") (pin "2") (pinfunction "S_2") (pintype "bidirectional"))
      (node (ref "Q8") (pin "2") (pinfunction "S_2") (pintype "bidirectional"))
      (node (ref "Q9") (pin "2") (pinfunction "S_2") (pintype "bidirectional"))
      (node (ref "R1") (pin "1") (pinfunction "1_1") (pintype "passive"))
      (node (ref "R10") (pin "1") (pinfunction "1_1") (pintype "passive"))
      (node (ref "R11") (pin "1") (pinfunction "1_1") (pintype "passive"))
      (node (ref "R12") (pin "1") (pinfunction "1_1") (pintype "passive"))
      (node (ref "R13") (pin "1") (pinfunction "1_1") (pintype "passive"))
      (node (ref "R14") (pin "1") (pinfunction "1_1") (pintype "passive"))
      (node (ref "R15") (pin "1") (pinfunction "1_1") (pintype "passive"))
      (node (ref "R16") (pin "1") (pinfunction "1_1") (pintype "passive"))
      (node (ref "R2") (pin "2") (pinfunction "2_2") (pintype "passive"))
      (node (ref "R21") (pin "2") (pinfunction "2_2") (pintype "passive"))
      (node (ref "R22") (pin "2") (pinfunction "2_2") (pintype "passive"))
      (node (ref "R24") (pin "2") (pinfunction "2_2") (pintype "passive"))
      (node (ref "R3") (pin "2") (pinfunction "2_2") (pintype "passive"))
      (node (ref "R34") (pin "1") (pinfunction "1_1") (pintype "passive"))
      (node (ref "R36") (pin "2") (pinfunction "2_2") (pintype "passive"))
      (node (ref "R38") (pin "2") (pinfunction "2_2") (pintype "passive"))
      (node (ref "R39") (pin "2") (pinfunction "2_2") (pintype "passive"))
      (node (ref "R4") (pin "2") (pinfunction "2_2") (pintype "passive"))
      (node (ref "R46") (pin "1") (pinfunction "A_1") (pintype "passive"))
      (node (ref "R5") (pin "2") (pinfunction "2_2") (pintype "passive"))
      (node (ref "R58") (pin "1") (pinfunction "1_1") (pintype "passive"))
      (node (ref "R59") (pin "2") (pinfunction "2_2") (pintype "passive"))
      (node (ref "R6") (pin "2") (pinfunction "2_2") (pintype "passive"))
      (node (ref "R60") (pin "2") (pinfunction "2_2") (pintype "passive"))
      (node (ref "R7") (pin "2") (pinfunction "2_2") (pintype "passive"))
      (node (ref "R75") (pin "1") (pinfunction "1_1") (pintype "passive"))
      (node (ref "R8") (pin "2") (pinfunction "2_2") (pintype "passive"))
      (node (ref "R9") (pin "2") (pinfunction "2_2") (pintype "passive"))
      (node (ref "S2") (pin "1") (pinfunction "1_1") (pintype "passive"))
      (node (ref "U$1") (pin "P$2") (pinfunction "P$2_P$2") (pintype "bidirectional"))
      (node (ref "U1") (pin "1") (pinfunction "GND_1") (pintype "power_in"))
      (node (ref "U1") (pin "6") (pinfunction "VPRG_6") (pintype "input"))
      (node (ref "U1") (pin "EXP") (pinfunction "GND_EXP") (pintype "power_in"))
      (node (ref "U2") (pin "21") (pinfunction "GND_21") (pintype "passive"))
      (node (ref "U2") (pin "3") (pinfunction "GND_2_3") (pintype "passive"))
      (node (ref "U2") (pin "5") (pinfunction "GND_3_5") (pintype "passive"))
      (node (ref "U3") (pin "1") (pinfunction "GND_1") (pintype "power_in"))
      (node (ref "U3") (pin "6") (pinfunction "VPRG_6") (pintype "input"))
      (node (ref "U3") (pin "EXP") (pinfunction "GND_EXP") (pintype "power_in"))
      (node (ref "Y1") (pin "2") (pinfunction "2_2") (pintype "passive"))
    )
    (net (code "6") (name "GSCLK") (class "Default")
      (node (ref "U1") (pin "25") (pinfunction "GSCLK_25") (pintype "input"))
      (node (ref "U2") (pin "1") (pinfunction "PD3_1") (pintype "bidirectional"))
      (node (ref "U3") (pin "25") (pinfunction "GSCLK_25") (pintype "input"))
    )
    (net (code "7") (name "H_RXD") (class "Default")
      (node (ref "Q23") (pin "3") (pinfunction "D_3") (pintype "passive"))
      (node (ref "R44") (pin "2") (pinfunction "2_2") (pintype "passive"))
      (node (ref "U2") (pin "30") (pinfunction "PD0_30") (pintype "bidirectional"))
    )
    (net (code "8") (name "H_TXD") (class "Default")
      (node (ref "Q22") (pin "3") (pinfunction "D_3") (pintype "passive"))
      (node (ref "R26") (pin "2") (pinfunction "2_2") (pintype "passive"))
      (node (ref "U2") (pin "31") (pinfunction "PD1_31") (pintype "bidirectional"))
    )
    (net (code "9") (name "LIGHT_SENSOR") (class "Default")
      (node (ref "C6") (pin "2") (pinfunction "2_2") (pintype "passive"))
      (node (ref "J19") (pin "2") (pinfunction "2_2") (pintype "passive"))
      (node (ref "R46") (pin "2") (pinfunction "S_2") (pintype "passive"))
      (node (ref "U2") (pin "23") (pinfunction "PC0_23") (pintype "bidirectional"))
    )
    (net (code "10") (name "L_RXD") (class "Default")
      (node (ref "J24") (pin "2") (pinfunction "2_2") (pintype "passive"))
      (node (ref "Q23") (pin "2") (pinfunction "S_2") (pintype "passive"))
      (node (ref "R43") (pin "2") (pinfunction "2_2") (pintype "passive"))
    )
    (net (code "11") (name "L_TXD") (class "Default")
      (node (ref "J24") (pin "1") (pinfunction "1_1") (pintype "passive"))
      (node (ref "Q22") (pin "2") (pinfunction "S_2") (pintype "passive"))
      (node (ref "R25") (pin "2") (pinfunction "2_2") (pintype "passive"))
    )
    (net (code "12") (name "MISO") (class "Default")
      (node (ref "J18") (pin "P$1") (pinfunction "1_P$1") (pintype "bidirectional"))
      (node (ref "U2") (pin "16") (pinfunction "PB4_16") (pintype "bidirectional"))
    )
    (net (code "13") (name "MOSI_SIN") (class "Default")
      (node (ref "J18") (pin "P$4") (pinfunction "4_P$4") (pintype "bidirectional"))
      (node (ref "U1") (pin "5") (pinfunction "SIN_5") (pintype "input"))
      (node (ref "U2") (pin "15") (pinfunction "PB3_15") (pintype "bidirectional"))
    )
    (net (code "14") (name "Net-(D1-PadA)") (class "Default")
      (node (ref "D1") (pin "A") (pinfunction "A_A") (pintype "passive"))
      (node (ref "LED2") (pin "A") (pinfunction "A_A") (pintype "passive"))
      (node (ref "U$1") (pin "P$1") (pinfunction "P$1_P$1") (pintype "bidirectional"))
    )
    (net (code "15") (name "Net-(D100-PadC)") (class "Default")
      (node (ref "D100") (pin "C") (pinfunction "C_C") (pintype "passive"))
      (node (ref "D102") (pin "A") (pinfunction "A_A") (pintype "passive"))
      (node (ref "R109") (pin "2") (pinfunction "2_2") (pintype "passive"))
      (node (ref "R116") (pin "1") (pinfunction "1_1") (pintype "passive"))
    )
    (net (code "16") (name "Net-(D101-PadC)") (class "Default")
      (node (ref "D101") (pin "C") (pinfunction "C_C") (pintype "passive"))
      (node (ref "D103") (pin "A") (pinfunction "A_A") (pintype "passive"))
      (node (ref "R110") (pin "2") (pinfunction "2_2") (pintype "passive"))
      (node (ref "R115") (pin "1") (pinfunction "1_1") (pintype "passive"))
    )
    (net (code "17") (name "Net-(IC2-IN)") (class "Default")
      (node (ref "C1") (pin "2") (pinfunction "2_2") (pintype "passive"))
      (node (ref "D1") (pin "C") (pinfunction "C_C") (pintype "passive"))
      (node (ref "IC2") (pin "3") (pinfunction "IN_3") (pintype "input"))
    )
    (net (code "18") (name "Net-(IC2-OUT)") (class "Default")
      (node (ref "C4") (pin "+") (pinfunction "+_+") (pintype "passive"))
      (node (ref "FUSE1") (pin "1") (pinfunction "1_1") (pintype "passive"))
      (node (ref "IC2") (pin "4") (pinfunction "OUT_4") (pintype "passive"))
    )
    (net (code "19") (name "Net-(IC4A-I)") (class "Default")
      (node (ref "IC4") (pin "2") (pinfunction "I_2") (pintype "input"))
      (node (ref "R42") (pin "1") (pinfunction "1_1") (pintype "passive"))
      (node (ref "U3") (pin "9") (pinfunction "OUT2_9") (pintype "output"))
    )
    (net (code "20") (name "Net-(IC4A-O)") (class "Default")
      (node (ref "IC4") (pin "4") (pinfunction "O_4") (pintype "output"))
      (node (ref "Q19") (pin "1") (pinfunction "G_1") (pintype "bidirectional"))
      (node (ref "R60") (pin "1") (pinfunction "1_1") (pintype "passive"))
    )
    (net (code "21") (name "Net-(IC100A-I)") (class "Default")
      (node (ref "IC100") (pin "1") (pinfunction "I_1") (pintype "input"))
      (node (ref "R18") (pin "1") (pinfunction "1_1") (pintype "passive"))
      (node (ref "U1") (pin "13") (pinfunction "OUT6_13") (pintype "output"))
    )
    (net (code "22") (name "Net-(IC100A-O)") (class "Default")
      (node (ref "IC100") (pin "2") (pinfunction "O_2") (pintype "output"))
      (node (ref "Q7") (pin "1") (pinfunction "G_1") (pintype "bidirectional"))
      (node (ref "R7") (pin "1") (pinfunction "1_1") (pintype "passive"))
    )
    (net (code "23") (name "Net-(IC100B-I)") (class "Default")
      (node (ref "IC100") (pin "3") (pinfunction "I_3") (pintype "input"))
      (node (ref "R17") (pin "1") (pinfunction "1_1") (pintype "passive"))
      (node (ref "U1") (pin "14") (pinfunction "OUT7_14") (pintype "output"))
    )
    (net (code "24") (name "Net-(IC100B-O)") (class "Default")
      (node (ref "IC100") (pin "4") (pinfunction "O_4") (pintype "output"))
      (node (ref "Q8") (pin "1") (pinfunction "G_1") (pintype "bidirectional"))
      (node (ref "R8") (pin "1") (pinfunction "1_1") (pintype "passive"))
    )
    (net (code "25") (name "Net-(IC100C-I)") (class "Default")
      (node (ref "IC100") (pin "5") (pinfunction "I_5") (pintype "input"))
      (node (ref "R102") (pin "2") (pinfunction "2_2") (pintype "passive"))
      (node (ref "U1") (pin "15") (pinfunction "OUT8_15") (pintype "output"))
    )
    (net (code "26") (name "Net-(IC100C-O)") (class "Default")
      (node (ref "IC100") (pin "6") (pinfunction "O_6") (pintype "output"))
      (node (ref "Q9") (pin "1") (pinfunction "G_1") (pintype "bidirectional"))
      (node (ref "R9") (pin "1") (pinfunction "1_1") (pintype "passive"))
    )
    (net (code "27") (name "Net-(IC100D-I)") (class "Default")
      (node (ref "IC100") (pin "9") (pinfunction "I_9") (pintype "input"))
      (node (ref "R105") (pin "2") (pinfunction "2_2") (pintype "passive"))
      (node (ref "U1") (pin "16") (pinfunction "OUT9_16") (pintype "output"))
    )
    (net (code "28") (name "Net-(IC100D-O)") (class "Default")
      (node (ref "IC100") (pin "8") (pinfunction "O_8") (pintype "output"))
      (node (ref "Q10") (pin "1") (pinfunction "G_1") (pintype "bidirectional"))
      (node (ref "R10") (pin "2") (pinfunction "2_2") (pintype "passive"))
    )
    (net (code "29") (name "Net-(IC100E-I)") (class "Default")
      (node (ref "IC100") (pin "11") (pinfunction "I_11") (pintype "input"))
      (node (ref "R103") (pin "2") (pinfunction "2_2") (pintype "passive"))
      (node (ref "U1") (pin "17") (pinfunction "OUT10_17") (pintype "output"))
    )
    (net (code "30") (name "Net-(IC100E-O)") (class "Default")
      (node (ref "IC100") (pin "10") (pinfunction "O_10") (pintype "output"))
      (node (ref "Q11") (pin "1") (pinfunction "G_1") (pintype "bidirectional"))
      (node (ref "R11") (pin "2") (pinfunction "2_2") (pintype "passive"))
    )
    (net (code "31") (name "Net-(IC100F-I)") (class "Default")
      (node (ref "IC100") (pin "13") (pinfunction "I_13") (pintype "input"))
      (node (ref "R101") (pin "2") (pinfunction "2_2") (pintype "passive"))
      (node (ref "U1") (pin "18") (pinfunction "OUT11_18") (pintype "output"))
    )
    (net (code "32") (name "Net-(IC100F-O)") (class "Default")
      (node (ref "IC100") (pin "12") (pinfunction "O_12") (pintype "output"))
      (node (ref "Q12") (pin "1") (pinfunction "G_1") (pintype "bidirectional"))
      (node (ref "R12") (pin "2") (pinfunction "2_2") (pintype "passive"))
    )
    (net (code "33") (name "Net-(IC101A-I)") (class "Default")
      (node (ref "IC101") (pin "1") (pinfunction "I_1") (pintype "input"))
      (node (ref "R32") (pin "1") (pinfunction "1_1") (pintype "passive"))
      (node (ref "U1") (pin "7") (pinfunction "OUT0_7") (pintype "output"))
    )
    (net (code "34") (name "Net-(IC101A-O)") (class "Default")
      (node (ref "IC101") (pin "2") (pinfunction "O_2") (pintype "output"))
      (node (ref "Q1") (pin "1") (pinfunction "G_1") (pintype "bidirectional"))
      (node (ref "R1") (pin "2") (pinfunction "2_2") (pintype "passive"))
    )
    (net (code "35") (name "Net-(IC101B-I)") (class "Default")
      (node (ref "IC101") (pin "3") (pinfunction "I_3") (pintype "input"))
      (node (ref "R31") (pin "1") (pinfunction "1_1") (pintype "passive"))
      (node (ref "U1") (pin "8") (pinfunction "OUT1_8") (pintype "output"))
    )
    (net (code "36") (name "Net-(IC101B-O)") (class "Default")
      (node (ref "IC101") (pin "4") (pinfunction "O_4") (pintype "output"))
      (node (ref "Q2") (pin "1") (pinfunction "G_1") (pintype "bidirectional"))
      (node (ref "R2") (pin "1") (pinfunction "1_1") (pintype "passive"))
    )
    (net (code "37") (name "Net-(IC101C-I)") (class "Default")
      (node (ref "IC101") (pin "5") (pinfunction "I_5") (pintype "input"))
      (node (ref "R29") (pin "1") (pinfunction "1_1") (pintype "passive"))
      (node (ref "U1") (pin "9") (pinfunction "OUT2_9") (pintype "output"))
    )
    (net (code "38") (name "Net-(IC101C-O)") (class "Default")
      (node (ref "IC101") (pin "6") (pinfunction "O_6") (pintype "output"))
      (node (ref "Q3") (pin "1") (pinfunction "G_1") (pintype "bidirectional"))
      (node (ref "R3") (pin "1") (pinfunction "1_1") (pintype "passive"))
    )
    (net (code "39") (name "Net-(IC101D-I)") (class "Default")
      (node (ref "IC101") (pin "9") (pinfunction "I_9") (pintype "input"))
      (node (ref "R28") (pin "1") (pinfunction "1_1") (pintype "passive"))
      (node (ref "U1") (pin "10") (pinfunction "OUT3_10") (pintype "output"))
    )
    (net (code "40") (name "Net-(IC101D-O)") (class "Default")
      (node (ref "IC101") (pin "8") (pinfunction "O_8") (pintype "output"))
      (node (ref "Q4") (pin "1") (pinfunction "G_1") (pintype "bidirectional"))
      (node (ref "R4") (pin "1") (pinfunction "1_1") (pintype "passive"))
    )
    (net (code "41") (name "Net-(IC101E-I)") (class "Default")
      (node (ref "IC101") (pin "11") (pinfunction "I_11") (pintype "input"))
      (node (ref "R20") (pin "1") (pinfunction "1_1") (pintype "passive"))
      (node (ref "U1") (pin "11") (pinfunction "OUT4_11") (pintype "output"))
    )
    (net (code "42") (name "Net-(IC101E-O)") (class "Default")
      (node (ref "IC101") (pin "10") (pinfunction "O_10") (pintype "output"))
      (node (ref "Q5") (pin "1") (pinfunction "G_1") (pintype "bidirectional"))
      (node (ref "R5") (pin "1") (pinfunction "1_1") (pintype "passive"))
    )
    (net (code "43") (name "Net-(IC101F-I)") (class "Default")
      (node (ref "IC101") (pin "13") (pinfunction "I_13") (pintype "input"))
      (node (ref "R19") (pin "1") (pinfunction "1_1") (pintype "passive"))
      (node (ref "U1") (pin "12") (pinfunction "OUT5_12") (pintype "output"))
    )
    (net (code "44") (name "Net-(IC101F-O)") (class "Default")
      (node (ref "IC101") (pin "12") (pinfunction "O_12") (pintype "output"))
      (node (ref "Q6") (pin "1") (pinfunction "G_1") (pintype "bidirectional"))
      (node (ref "R6") (pin "1") (pinfunction "1_1") (pintype "passive"))
    )
    (net (code "45") (name "Net-(IC102A-I)") (class "Default")
      (node (ref "IC102") (pin "1") (pinfunction "I_1") (pintype "input"))
      (node (ref "R104") (pin "2") (pinfunction "2_2") (pintype "passive"))
      (node (ref "U1") (pin "19") (pinfunction "OUT12_19") (pintype "output"))
    )
    (net (code "46") (name "Net-(IC102A-O)") (class "Default")
      (node (ref "IC102") (pin "2") (pinfunction "O_2") (pintype "output"))
      (node (ref "Q13") (pin "1") (pinfunction "G_1") (pintype "bidirectional"))
      (node (ref "R13") (pin "2") (pinfunction "2_2") (pintype "passive"))
    )
    (net (code "47") (name "Net-(IC102B-I)") (class "Default")
      (node (ref "IC102") (pin "3") (pinfunction "I_3") (pintype "input"))
      (node (ref "R106") (pin "2") (pinfunction "2_2") (pintype "passive"))
      (node (ref "U1") (pin "20") (pinfunction "OUT13_20") (pintype "output"))
    )
    (net (code "48") (name "Net-(IC102B-O)") (class "Default")
      (node (ref "IC102") (pin "4") (pinfunction "O_4") (pintype "output"))
      (node (ref "Q14") (pin "1") (pinfunction "G_1") (pintype "bidirectional"))
      (node (ref "R14") (pin "2") (pinfunction "2_2") (pintype "passive"))
    )
    (net (code "49") (name "Net-(IC102C-I)") (class "Default")
      (node (ref "IC102") (pin "5") (pinfunction "I_5") (pintype "input"))
      (node (ref "R108") (pin "2") (pinfunction "2_2") (pintype "passive"))
      (node (ref "U1") (pin "21") (pinfunction "OUT14_21") (pintype "output"))
    )
    (net (code "50") (name "Net-(IC102C-O)") (class "Default")
      (node (ref "IC102") (pin "6") (pinfunction "O_6") (pintype "output"))
      (node (ref "Q15") (pin "1") (pinfunction "G_1") (pintype "bidirectional"))
      (node (ref "R15") (pin "2") (pinfunction "2_2") (pintype "passive"))
    )
    (net (code "51") (name "Net-(IC102D-I)") (class "Default")
      (node (ref "IC102") (pin "9") (pinfunction "I_9") (pintype "input"))
      (node (ref "R107") (pin "2") (pinfunction "2_2") (pintype "passive"))
      (node (ref "U1") (pin "22") (pinfunction "OUT15_22") (pintype "output"))
    )
    (net (code "52") (name "Net-(IC102D-O)") (class "Default")
      (node (ref "IC102") (pin "8") (pinfunction "O_8") (pintype "output"))
      (node (ref "Q16") (pin "1") (pinfunction "G_1") (pintype "bidirectional"))
      (node (ref "R16") (pin "2") (pinfunction "2_2") (pintype "passive"))
    )
    (net (code "53") (name "Net-(IC102E-I)") (class "Default")
      (node (ref "IC102") (pin "11") (pinfunction "I_11") (pintype "input"))
      (node (ref "R40") (pin "1") (pinfunction "1_1") (pintype "passive"))
      (node (ref "U3") (pin "7") (pinfunction "OUT0_7") (pintype "output"))
    )
    (net (code "54") (name "Net-(IC102E-O)") (class "Default")
      (node (ref "IC102") (pin "10") (pinfunction "O_10") (pintype "output"))
      (node (ref "Q17") (pin "1") (pinfunction "G_1") (pintype "bidirectional"))
      (node (ref "R58") (pin "2") (pinfunction "2_2") (pintype "passive"))
    )
    (net (code "55") (name "Net-(IC102F-I)") (class "Default")
      (node (ref "IC102") (pin "13") (pinfunction "I_13") (pintype "input"))
      (node (ref "R41") (pin "1") (pinfunction "1_1") (pintype "passive"))
      (node (ref "U3") (pin "8") (pinfunction "OUT1_8") (pintype "output"))
    )
    (net (code "56") (name "Net-(IC102F-O)") (class "Default")
      (node (ref "IC102") (pin "12") (pinfunction "O_12") (pintype "output"))
      (node (ref "Q18") (pin "1") (pinfunction "G_1") (pintype "bidirectional"))
      (node (ref "R59") (pin "1") (pinfunction "1_1") (pintype "passive"))
    )
    (net (code "57") (name "Net-(J20-Pad1)") (class "Default")
      (node (ref "J20") (pin "1") (pinfunction "1_1") (pintype "passive"))
      (node (ref "R116") (pin "2") (pinfunction "2_2") (pintype "passive"))
    )
    (net (code "58") (name "Net-(J21-Pad1)") (class "Default")
      (node (ref "J21") (pin "1") (pinfunction "1_1") (pintype "passive"))
      (node (ref "R115") (pin "2") (pinfunction "2_2") (pintype "passive"))
    )
    (net (code "59") (name "Net-(LED1-PadC)") (class "Default")
      (node (ref "LED1") (pin "C") (pinfunction "C_C") (pintype "passive"))
      (node (ref "R38") (pin "1") (pinfunction "1_1") (pintype "passive"))
    )
    (net (code "60") (name "Net-(LED2-PadC)") (class "Default")
      (node (ref "LED2") (pin "C") (pinfunction "C_C") (pintype "passive"))
      (node (ref "R39") (pin "1") (pinfunction "1_1") (pintype "passive"))
    )
    (net (code "61") (name "Net-(Q1-D)") (class "Default")
      (node (ref "J1") (pin "1") (pinfunction "1_1") (pintype "passive"))
      (node (ref "Q1") (pin "3") (pinfunction "D_3") (pintype "bidirectional"))
    )
    (net (code "62") (name "Net-(Q2-D)") (class "Default")
      (node (ref "J1") (pin "2") (pinfunction "2_2") (pintype "passive"))
      (node (ref "Q2") (pin "3") (pinfunction "D_3") (pintype "bidirectional"))
    )
    (net (code "63") (name "Net-(Q3-D)") (class "Default")
      (node (ref "J2") (pin "1") (pinfunction "1_1") (pintype "passive"))
      (node (ref "Q3") (pin "3") (pinfunction "D_3") (pintype "bidirectional"))
    )
    (net (code "64") (name "Net-(Q4-D)") (class "Default")
      (node (ref "J2") (pin "2") (pinfunction "2_2") (pintype "passive"))
      (node (ref "Q4") (pin "3") (pinfunction "D_3") (pintype "bidirectional"))
    )
    (net (code "65") (name "Net-(Q5-D)") (class "Default")
      (node (ref "J3") (pin "1") (pinfunction "1_1") (pintype "passive"))
      (node (ref "Q5") (pin "3") (pinfunction "D_3") (pintype "bidirectional"))
    )
    (net (code "66") (name "Net-(Q6-D)") (class "Default")
      (node (ref "J3") (pin "2") (pinfunction "2_2") (pintype "passive"))
      (node (ref "Q6") (pin "3") (pinfunction "D_3") (pintype "bidirectional"))
    )
    (net (code "67") (name "Net-(Q7-D)") (class "Default")
      (node (ref "J4") (pin "1") (pinfunction "1_1") (pintype "passive"))
      (node (ref "Q7") (pin "3") (pinfunction "D_3") (pintype "bidirectional"))
    )
    (net (code "68") (name "Net-(Q8-D)") (class "Default")
      (node (ref "J4") (pin "2") (pinfunction "2_2") (pintype "passive"))
      (node (ref "Q8") (pin "3") (pinfunction "D_3") (pintype "bidirectional"))
    )
    (net (code "69") (name "Net-(Q9-D)") (class "Default")
      (node (ref "J5") (pin "1") (pinfunction "1_1") (pintype "passive"))
      (node (ref "Q9") (pin "3") (pinfunction "D_3") (pintype "bidirectional"))
    )
    (net (code "70") (name "Net-(Q10-D)") (class "Default")
      (node (ref "J5") (pin "2") (pinfunction "2_2") (pintype "passive"))
      (node (ref "Q10") (pin "3") (pinfunction "D_3") (pintype "bidirectional"))
    )
    (net (code "71") (name "Net-(Q11-D)") (class "Default")
      (node (ref "J6") (pin "1") (pinfunction "1_1") (pintype "passive"))
      (node (ref "Q11") (pin "3") (pinfunction "D_3") (pintype "bidirectional"))
    )
    (net (code "72") (name "Net-(Q12-D)") (class "Default")
      (node (ref "J6") (pin "2") (pinfunction "2_2") (pintype "passive"))
      (node (ref "Q12") (pin "3") (pinfunction "D_3") (pintype "bidirectional"))
    )
    (net (code "73") (name "Net-(Q13-D)") (class "Default")
      (node (ref "J7") (pin "1") (pinfunction "1_1") (pintype "passive"))
      (node (ref "Q13") (pin "3") (pinfunction "D_3") (pintype "bidirectional"))
    )
    (net (code "74") (name "Net-(Q14-D)") (class "Default")
      (node (ref "J7") (pin "2") (pinfunction "2_2") (pintype "passive"))
      (node (ref "Q14") (pin "3") (pinfunction "D_3") (pintype "bidirectional"))
    )
    (net (code "75") (name "Net-(Q15-D)") (class "Default")
      (node (ref "J8") (pin "1") (pinfunction "1_1") (pintype "passive"))
      (node (ref "Q15") (pin "3") (pinfunction "D_3") (pintype "bidirectional"))
    )
    (net (code "76") (name "Net-(Q16-D)") (class "Default")
      (node (ref "J8") (pin "2") (pinfunction "2_2") (pintype "passive"))
      (node (ref "Q16") (pin "3") (pinfunction "D_3") (pintype "bidirectional"))
    )
    (net (code "77") (name "Net-(Q17-D)") (class "Default")
      (node (ref "J9") (pin "1") (pinfunction "1_1") (pintype "passive"))
      (node (ref "Q17") (pin "3") (pinfunction "D_3") (pintype "bidirectional"))
    )
    (net (code "78") (name "Net-(Q18-D)") (class "Default")
      (node (ref "J9") (pin "2") (pinfunction "2_2") (pintype "passive"))
      (node (ref "Q18") (pin "3") (pinfunction "D_3") (pintype "bidirectional"))
    )
    (net (code "79") (name "Net-(Q19-D)") (class "Default")
      (node (ref "J10") (pin "1") (pinfunction "1_1") (pintype "passive"))
      (node (ref "Q19") (pin "3") (pinfunction "D_3") (pintype "bidirectional"))
    )
    (net (code "80") (name "Net-(Q20-D)") (class "Default")
      (node (ref "D2") (pin "A") (pinfunction "A_A") (pintype "passive"))
      (node (ref "J11") (pin "1") (pinfunction "1_1") (pintype "passive"))
      (node (ref "Q20") (pin "3") (pinfunction "D_3") (pintype "bidirectional"))
    )
    (net (code "81") (name "Net-(Q21-D)") (class "Default")
      (node (ref "D3") (pin "A") (pinfunction "A_A") (pintype "passive"))
      (node (ref "J12") (pin "1") (pinfunction "1_1") (pintype "passive"))
      (node (ref "Q21") (pin "3") (pinfunction "D_3") (pintype "bidirectional"))
    )
    (net (code "82") (name "Net-(Q100-S)") (class "Default")
      (node (ref "J23") (pin "2") (pinfunction "2_2") (pintype "passive"))
      (node (ref "Q100") (pin "2") (pinfunction "S_2") (pintype "passive"))
      (node (ref "R117") (pin "1") (pinfunction "1_1") (pintype "passive"))
    )
    (net (code "83") (name "Net-(Q101-S)") (class "Default")
      (node (ref "J22") (pin "2") (pinfunction "2_2") (pintype "passive"))
      (node (ref "Q101") (pin "2") (pinfunction "S_2") (pintype "passive"))
      (node (ref "R118") (pin "1") (pinfunction "1_1") (pintype "passive"))
    )
    (net (code "84") (name "Net-(U1-IREF)") (class "Default")
      (node (ref "R34") (pin "2") (pinfunction "2_2") (pintype "passive"))
      (node (ref "U1") (pin "27") (pinfunction "IREF_27") (pintype "passive"))
    )
    (net (code "85") (name "Net-(U2-AREF)") (class "Default")
      (node (ref "C3") (pin "2") (pinfunction "2_2") (pintype "passive"))
      (node (ref "U2") (pin "20") (pinfunction "AREF_20") (pintype "input"))
    )
    (net (code "86") (name "Net-(U2-AVCC)") (class "Default")
      (node (ref "C11") (pin "1") (pinfunction "1_1") (pintype "passive"))
      (node (ref "L1") (pin "1") (pinfunction "1_1") (pintype "passive"))
      (node (ref "U2") (pin "18") (pinfunction "AVCC_18") (pintype "power_in"))
    )
    (net (code "87") (name "Net-(U2-PB6)") (class "Default")
      (node (ref "U2") (pin "7") (pinfunction "PB6_7") (pintype "bidirectional"))
      (node (ref "Y1") (pin "1") (pinfunction "1_1") (pintype "passive"))
    )
    (net (code "88") (name "Net-(U2-PB7)") (class "Default")
      (node (ref "U2") (pin "8") (pinfunction "PB7_8") (pintype "bidirectional"))
      (node (ref "Y1") (pin "3") (pinfunction "3_3") (pintype "passive"))
    )
    (net (code "89") (name "Net-(U3-IREF)") (class "Default")
      (node (ref "R75") (pin "2") (pinfunction "2_2") (pintype "passive"))
      (node (ref "U3") (pin "27") (pinfunction "IREF_27") (pintype "passive"))
    )
    (net (code "90") (name "RELAY0") (class "Default")
      (node (ref "Q20") (pin "1") (pinfunction "G_1") (pintype "bidirectional"))
      (node (ref "R21") (pin "1") (pinfunction "1_1") (pintype "passive"))
      (node (ref "U2") (pin "25") (pinfunction "PC2_25") (pintype "bidirectional"))
    )
    (net (code "91") (name "RELAY1") (class "Default")
      (node (ref "Q21") (pin "1") (pinfunction "G_1") (pintype "bidirectional"))
      (node (ref "R22") (pin "1") (pinfunction "1_1") (pintype "passive"))
      (node (ref "U2") (pin "26") (pinfunction "PC3_26") (pintype "bidirectional"))
    )
    (net (code "92") (name "RESET") (class "Default")
      (node (ref "J18") (pin "P$5") (pinfunction "5_P$5") (pintype "bidirectional"))
      (node (ref "R35") (pin "2") (pinfunction "2_2") (pintype "passive"))
      (node (ref "S2") (pin "3") (pinfunction "2_3") (pintype "passive"))
      (node (ref "U2") (pin "29") (pinfunction "PC6_29") (pintype "bidirectional"))
    )
    (net (code "93") (name "SCLK") (class "Default")
      (node (ref "J18") (pin "P$3") (pinfunction "3_P$3") (pintype "bidirectional"))
      (node (ref "U1") (pin "4") (pinfunction "SCLK_4") (pintype "input"))
      (node (ref "U2") (pin "17") (pinfunction "PB5_17") (pintype "bidirectional"))
      (node (ref "U3") (pin "4") (pinfunction "SCLK_4") (pintype "input"))
    )
    (net (code "94") (name "SENSOR_BOTTOM") (class "Default")
      (node (ref "Q100") (pin "3") (pinfunction "D_3") (pintype "passive"))
      (node (ref "R111") (pin "1") (pinfunction "1_1") (pintype "passive"))
      (node (ref "U2") (pin "12") (pinfunction "PB0_12") (pintype "bidirectional"))
    )
    (net (code "95") (name "SENSOR_TOP") (class "Default")
      (node (ref "Q101") (pin "3") (pinfunction "D_3") (pintype "passive"))
      (node (ref "R112") (pin "1") (pinfunction "1_1") (pintype "passive"))
      (node (ref "U2") (pin "11") (pinfunction "PD7_11") (pintype "bidirectional"))
    )
    (net (code "96") (name "SOUT") (class "Default")
      (node (ref "U1") (pin "24") (pinfunction "SOUT_24") (pintype "output"))
      (node (ref "U3") (pin "5") (pinfunction "SIN_5") (pintype "input"))
    )
    (net (code "97") (name "SWITCH_BOTTOM") (class "Default")
      (node (ref "C104") (pin "2") (pinfunction "2_2") (pintype "passive"))
      (node (ref "R110") (pin "1") (pinfunction "1_1") (pintype "passive"))
      (node (ref "R113") (pin "1") (pinfunction "1_1") (pintype "passive"))
      (node (ref "U2") (pin "10") (pinfunction "PD6_10") (pintype "bidirectional"))
    )
    (net (code "98") (name "SWITCH_TOP") (class "Default")
      (node (ref "C103") (pin "2") (pinfunction "2_2") (pintype "passive"))
      (node (ref "R109") (pin "1") (pinfunction "1_1") (pintype "passive"))
      (node (ref "R114") (pin "1") (pinfunction "1_1") (pintype "passive"))
      (node (ref "U2") (pin "9") (pinfunction "PD5_9") (pintype "bidirectional"))
    )
    (net (code "99") (name "XLAT") (class "Default")
      (node (ref "U1") (pin "3") (pinfunction "XLAT_3") (pintype "input"))
      (node (ref "U2") (pin "13") (pinfunction "PB1_13") (pintype "bidirectional"))
      (node (ref "U3") (pin "3") (pinfunction "XLAT_3") (pintype "input"))
    )
    (net (code "100") (name "unconnected-(J10-Pad2)") (class "Default")
      (node (ref "J10") (pin "2") (pinfunction "2_2") (pintype "passive"))
    )
    (net (code "101") (name "unconnected-(R46-E-Pad3)") (class "Default")
      (node (ref "R46") (pin "3") (pinfunction "E_3") (pintype "passive"))
    )
    (net (code "102") (name "unconnected-(U1-XERR-Pad23)") (class "Default")
      (node (ref "U1") (pin "23") (pinfunction "XERR_23") (pintype "output"))
    )
    (net (code "103") (name "unconnected-(U2-ADC6-Pad19)") (class "Default")
      (node (ref "U2") (pin "19") (pinfunction "ADC6_19") (pintype "input"))
    )
    (net (code "104") (name "unconnected-(U2-ADC7-Pad22)") (class "Default")
      (node (ref "U2") (pin "22") (pinfunction "ADC7_22") (pintype "input"))
    )
    (net (code "105") (name "unconnected-(U2-PC1-Pad24)") (class "Default")
      (node (ref "U2") (pin "24") (pinfunction "PC1_24") (pintype "bidirectional"))
    )
    (net (code "106") (name "unconnected-(U2-PC4-Pad27)") (class "Default")
      (node (ref "U2") (pin "27") (pinfunction "PC4_27") (pintype "bidirectional"))
    )
    (net (code "107") (name "unconnected-(U2-PC5-Pad28)") (class "Default")
      (node (ref "U2") (pin "28") (pinfunction "PC5_28") (pintype "bidirectional"))
    )
    (net (code "108") (name "unconnected-(U2-PD2-Pad32)") (class "Default")
      (node (ref "U2") (pin "32") (pinfunction "PD2_32") (pintype "bidirectional"))
    )
    (net (code "109") (name "unconnected-(U2-PD4-Pad2)") (class "Default")
      (node (ref "U2") (pin "2") (pinfunction "PD4_2") (pintype "bidirectional"))
    )
    (net (code "110") (name "unconnected-(U3-OUT3-Pad10)") (class "Default")
      (node (ref "U3") (pin "10") (pinfunction "OUT3_10") (pintype "output"))
    )
    (net (code "111") (name "unconnected-(U3-OUT4-Pad11)") (class "Default")
      (node (ref "U3") (pin "11") (pinfunction "OUT4_11") (pintype "output"))
    )
    (net (code "112") (name "unconnected-(U3-OUT5-Pad12)") (class "Default")
      (node (ref "U3") (pin "12") (pinfunction "OUT5_12") (pintype "output"))
    )
    (net (code "113") (name "unconnected-(U3-OUT6-Pad13)") (class "Default")
      (node (ref "U3") (pin "13") (pinfunction "OUT6_13") (pintype "output"))
    )
    (net (code "114") (name "unconnected-(U3-OUT7-Pad14)") (class "Default")
      (node (ref "U3") (pin "14") (pinfunction "OUT7_14") (pintype "output"))
    )
    (net (code "115") (name "unconnected-(U3-OUT8-Pad15)") (class "Default")
      (node (ref "U3") (pin "15") (pinfunction "OUT8_15") (pintype "output"))
    )
    (net (code "116") (name "unconnected-(U3-OUT9-Pad16)") (class "Default")
      (node (ref "U3") (pin "16") (pinfunction "OUT9_16") (pintype "output"))
    )
    (net (code "117") (name "unconnected-(U3-OUT10-Pad17)") (class "Default")
      (node (ref "U3") (pin "17") (pinfunction "OUT10_17") (pintype "output"))
    )
    (net (code "118") (name "unconnected-(U3-OUT11-Pad18)") (class "Default")
      (node (ref "U3") (pin "18") (pinfunction "OUT11_18") (pintype "output"))
    )
    (net (code "119") (name "unconnected-(U3-OUT12-Pad19)") (class "Default")
      (node (ref "U3") (pin "19") (pinfunction "OUT12_19") (pintype "output"))
    )
    (net (code "120") (name "unconnected-(U3-OUT13-Pad20)") (class "Default")
      (node (ref "U3") (pin "20") (pinfunction "OUT13_20") (pintype "output"))
    )
    (net (code "121") (name "unconnected-(U3-OUT14-Pad21)") (class "Default")
      (node (ref "U3") (pin "21") (pinfunction "OUT14_21") (pintype "output"))
    )
    (net (code "122") (name "unconnected-(U3-OUT15-Pad22)") (class "Default")
      (node (ref "U3") (pin "22") (pinfunction "OUT15_22") (pintype "output"))
    )
    (net (code "123") (name "unconnected-(U3-SOUT-Pad24)") (class "Default")
      (node (ref "U3") (pin "24") (pinfunction "SOUT_24") (pintype "output"))
    )
    (net (code "124") (name "unconnected-(U3-XERR-Pad23)") (class "Default")
      (node (ref "U3") (pin "23") (pinfunction "XERR_23") (pintype "output"))
    )
  )
)
